# pqxProbjSheet.net
KiCad netlist of a schematic drawn in Altium Designer
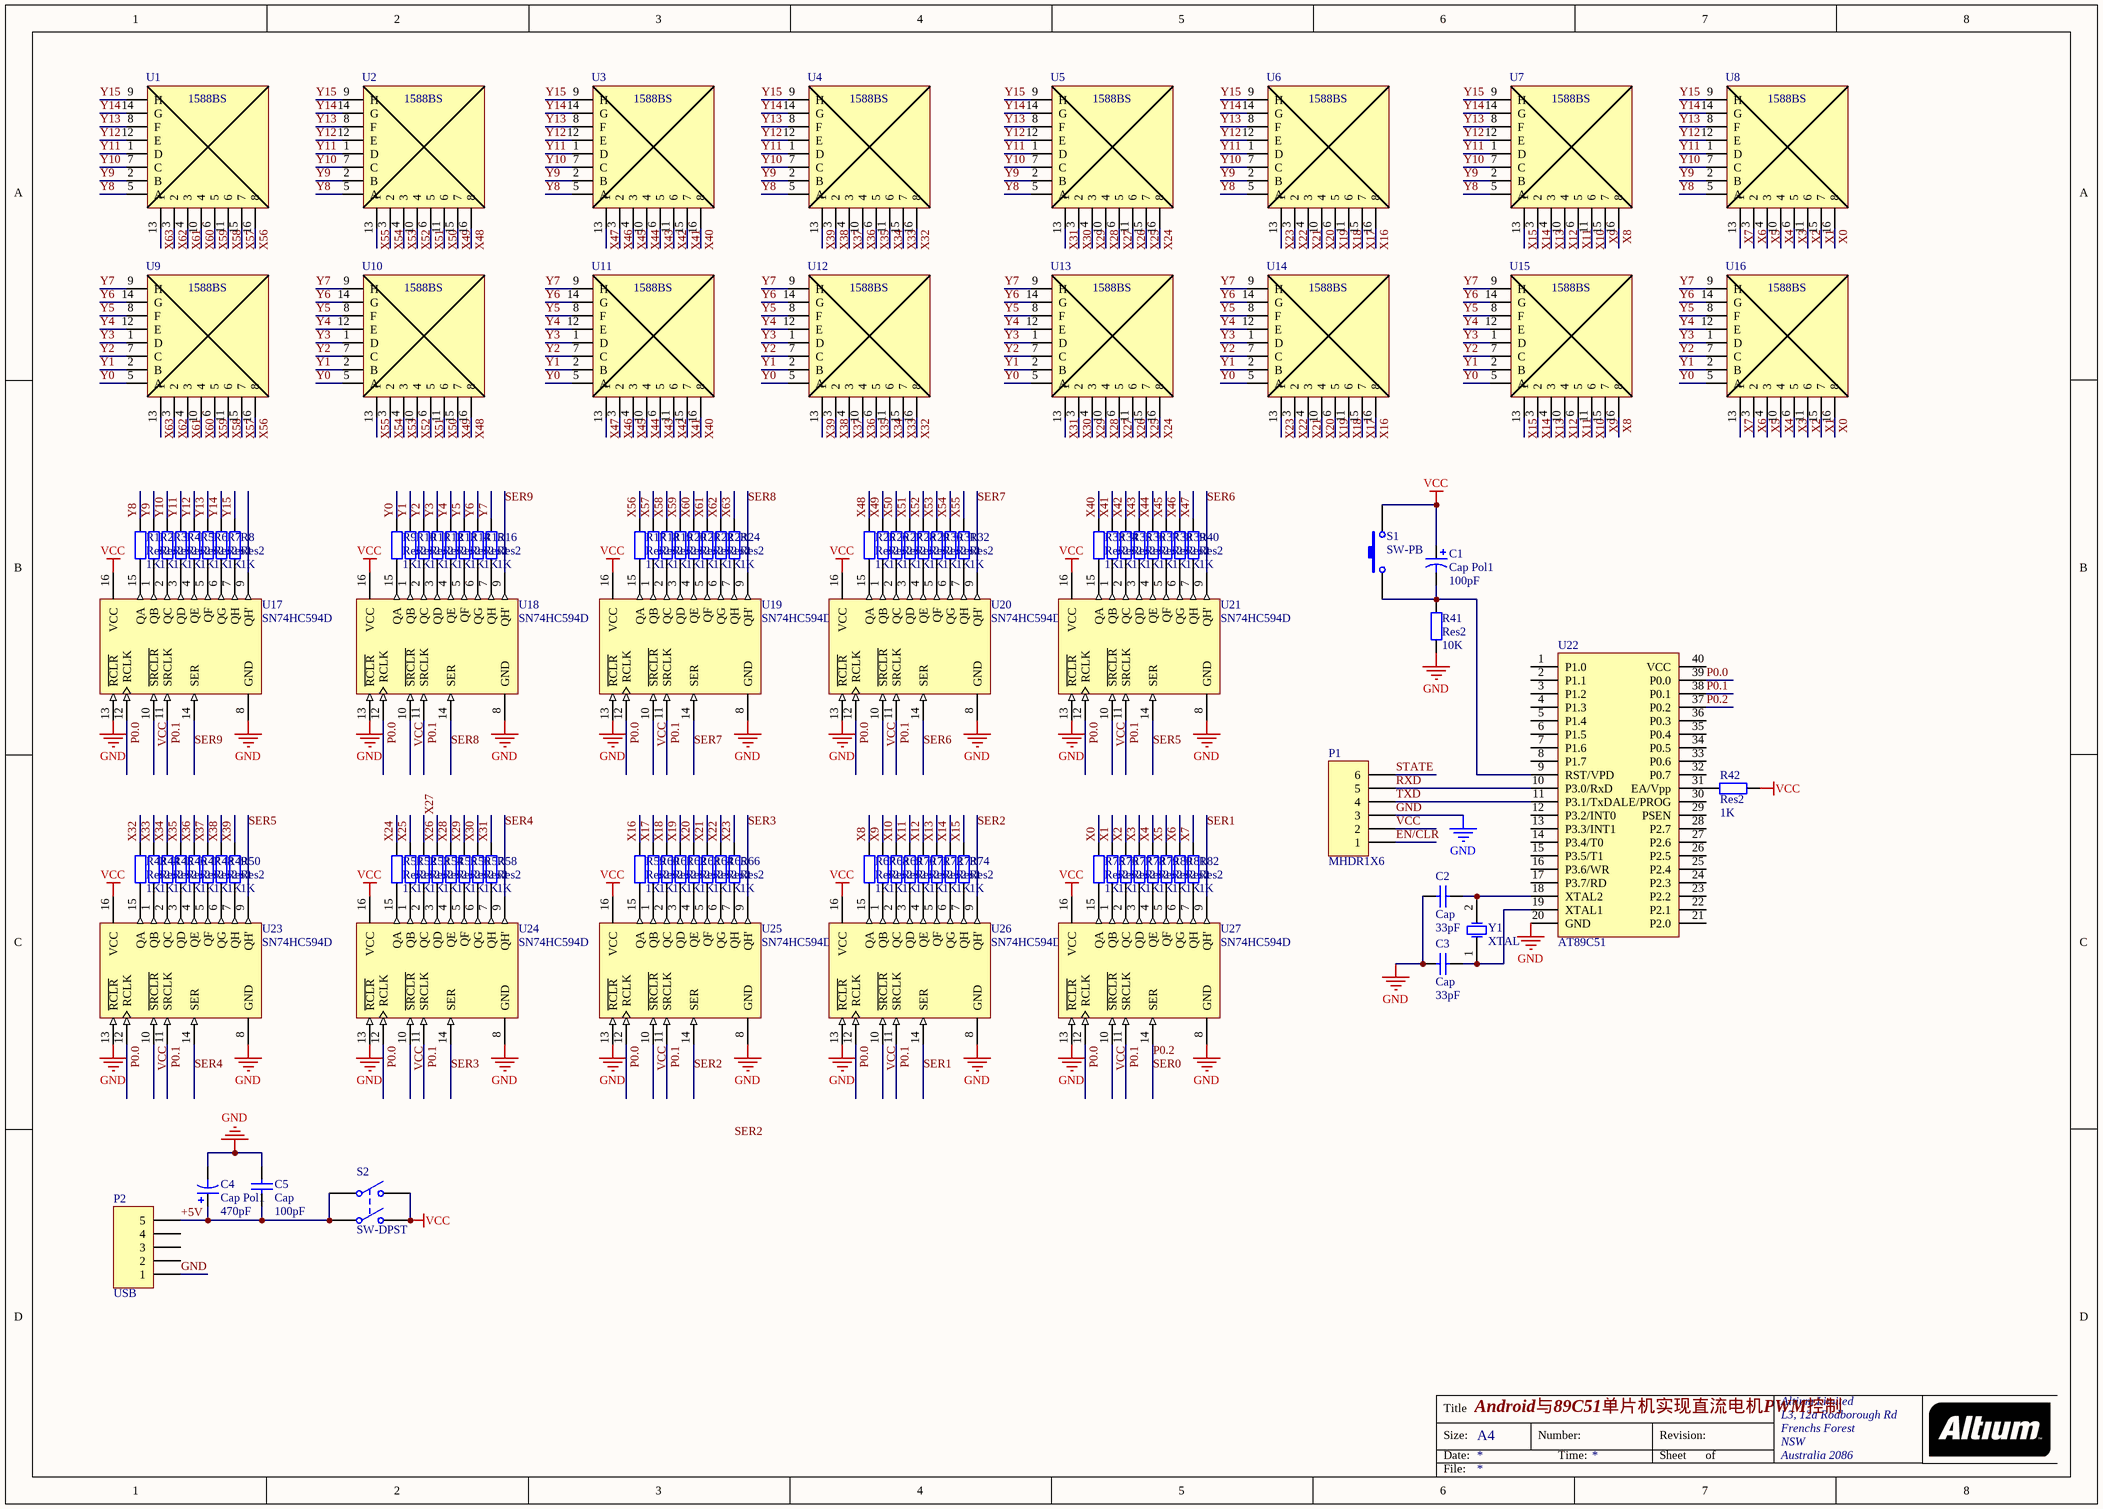
[diagram p0: pqxProbjSheet.SchDoc]

(export (version "E")
  (design (tool "Eeschema 10.0.6"))
  (components
    (comp (ref "C1")
      (value "Cap Pol1")
      (footprint "RB7.6-15")
      (description "Polarized Capacitor (Radial)")
      (fields (field (name "ALTIUM_VALUE") "100pF") (field (name "PUBLISHER") "Altium Limited"))
      (libsource (lib "Miscellaneous Devices") (part "Cap Pol1"))
    )
    (comp (ref "C2")
      (value "Cap")
      (footprint "RAD-0.3")
      (description "Capacitor")
      (fields (field (name "ALTIUM_VALUE") "33pF") (field (name "PUBLISHER") "Altium Limited"))
      (libsource (lib "Miscellaneous Devices") (part "Cap"))
    )
    (comp (ref "C3")
      (value "Cap")
      (footprint "RAD-0.3")
      (description "Capacitor")
      (fields (field (name "ALTIUM_VALUE") "33pF") (field (name "PUBLISHER") "Altium Limited"))
      (libsource (lib "Miscellaneous Devices") (part "Cap"))
    )
    (comp (ref "C4")
      (value "Cap Pol1")
      (footprint "RB7.6-15")
      (description "Polarized Capacitor (Radial)")
      (fields (field (name "ALTIUM_VALUE") "470pF") (field (name "PUBLISHER") "Altium Limited"))
      (libsource (lib "Miscellaneous Devices") (part "Cap Pol1"))
    )
    (comp (ref "C5")
      (value "Cap")
      (footprint "VP32-3.2")
      (description "Capacitor")
      (fields (field (name "ALTIUM_VALUE") "100pF") (field (name "PUBLISHER") "Altium Limited"))
      (libsource (lib "Miscellaneous Devices") (part "Cap"))
    )
    (comp (ref "P1")
      (value "MHDR1X6")
      (footprint "MHDR1X6")
      (description "Header, 6-Pin")
      (fields (field (name "PUBLISHER") "Altium Limited"))
      (libsource (lib "Miscellaneous Connectors") (part "MHDR1X6"))
    )
    (comp (ref "P2")
      (value "USB")
      (footprint "HDR1X5")
      (description "Header, 5-Pin, Right Angle")
      (fields (field (name "PUBLISHER") "Altium Limited"))
      (libsource (lib "Miscellaneous Connectors") (part "Header 5H"))
    )
    (comp (ref "R1")
      (value "Res2")
      (footprint "AXIAL-0.4")
      (description "Resistor")
      (fields (field (name "ALTIUM_VALUE") "1K") (field (name "PUBLISHER") "Altium Limited"))
      (libsource (lib "Miscellaneous Devices") (part "Res2"))
    )
    (comp (ref "R2")
      (value "Res2")
      (footprint "AXIAL-0.4")
      (description "Resistor")
      (fields (field (name "ALTIUM_VALUE") "1K") (field (name "PUBLISHER") "Altium Limited"))
      (libsource (lib "Miscellaneous Devices") (part "Res2"))
    )
    (comp (ref "R3")
      (value "Res2")
      (footprint "AXIAL-0.4")
      (description "Resistor")
      (fields (field (name "ALTIUM_VALUE") "1K") (field (name "PUBLISHER") "Altium Limited"))
      (libsource (lib "Miscellaneous Devices") (part "Res2"))
    )
    (comp (ref "R4")
      (value "Res2")
      (footprint "AXIAL-0.4")
      (description "Resistor")
      (fields (field (name "ALTIUM_VALUE") "1K") (field (name "PUBLISHER") "Altium Limited"))
      (libsource (lib "Miscellaneous Devices") (part "Res2"))
    )
    (comp (ref "R5")
      (value "Res2")
      (footprint "AXIAL-0.4")
      (description "Resistor")
      (fields (field (name "ALTIUM_VALUE") "1K") (field (name "PUBLISHER") "Altium Limited"))
      (libsource (lib "Miscellaneous Devices") (part "Res2"))
    )
    (comp (ref "R6")
      (value "Res2")
      (footprint "AXIAL-0.4")
      (description "Resistor")
      (fields (field (name "ALTIUM_VALUE") "1K") (field (name "PUBLISHER") "Altium Limited"))
      (libsource (lib "Miscellaneous Devices") (part "Res2"))
    )
    (comp (ref "R7")
      (value "Res2")
      (footprint "AXIAL-0.4")
      (description "Resistor")
      (fields (field (name "ALTIUM_VALUE") "1K") (field (name "PUBLISHER") "Altium Limited"))
      (libsource (lib "Miscellaneous Devices") (part "Res2"))
    )
    (comp (ref "R8")
      (value "Res2")
      (footprint "AXIAL-0.4")
      (description "Resistor")
      (fields (field (name "ALTIUM_VALUE") "1K") (field (name "PUBLISHER") "Altium Limited"))
      (libsource (lib "Miscellaneous Devices") (part "Res2"))
    )
    (comp (ref "R9")
      (value "Res2")
      (footprint "AXIAL-0.4")
      (description "Resistor")
      (fields (field (name "ALTIUM_VALUE") "1K") (field (name "PUBLISHER") "Altium Limited"))
      (libsource (lib "Miscellaneous Devices") (part "Res2"))
    )
    (comp (ref "R10")
      (value "Res2")
      (footprint "AXIAL-0.4")
      (description "Resistor")
      (fields (field (name "ALTIUM_VALUE") "1K") (field (name "PUBLISHER") "Altium Limited"))
      (libsource (lib "Miscellaneous Devices") (part "Res2"))
    )
    (comp (ref "R11")
      (value "Res2")
      (footprint "AXIAL-0.4")
      (description "Resistor")
      (fields (field (name "ALTIUM_VALUE") "1K") (field (name "PUBLISHER") "Altium Limited"))
      (libsource (lib "Miscellaneous Devices") (part "Res2"))
    )
    (comp (ref "R12")
      (value "Res2")
      (footprint "AXIAL-0.4")
      (description "Resistor")
      (fields (field (name "ALTIUM_VALUE") "1K") (field (name "PUBLISHER") "Altium Limited"))
      (libsource (lib "Miscellaneous Devices") (part "Res2"))
    )
    (comp (ref "R13")
      (value "Res2")
      (footprint "AXIAL-0.4")
      (description "Resistor")
      (fields (field (name "ALTIUM_VALUE") "1K") (field (name "PUBLISHER") "Altium Limited"))
      (libsource (lib "Miscellaneous Devices") (part "Res2"))
    )
    (comp (ref "R14")
      (value "Res2")
      (footprint "AXIAL-0.4")
      (description "Resistor")
      (fields (field (name "ALTIUM_VALUE") "1K") (field (name "PUBLISHER") "Altium Limited"))
      (libsource (lib "Miscellaneous Devices") (part "Res2"))
    )
    (comp (ref "R15")
      (value "Res2")
      (footprint "AXIAL-0.4")
      (description "Resistor")
      (fields (field (name "ALTIUM_VALUE") "1K") (field (name "PUBLISHER") "Altium Limited"))
      (libsource (lib "Miscellaneous Devices") (part "Res2"))
    )
    (comp (ref "R16")
      (value "Res2")
      (footprint "AXIAL-0.4")
      (description "Resistor")
      (fields (field (name "ALTIUM_VALUE") "1K") (field (name "PUBLISHER") "Altium Limited"))
      (libsource (lib "Miscellaneous Devices") (part "Res2"))
    )
    (comp (ref "R17")
      (value "Res2")
      (footprint "AXIAL-0.4")
      (description "Resistor")
      (fields (field (name "ALTIUM_VALUE") "1K") (field (name "PUBLISHER") "Altium Limited"))
      (libsource (lib "Miscellaneous Devices") (part "Res2"))
    )
    (comp (ref "R18")
      (value "Res2")
      (footprint "AXIAL-0.4")
      (description "Resistor")
      (fields (field (name "ALTIUM_VALUE") "1K") (field (name "PUBLISHER") "Altium Limited"))
      (libsource (lib "Miscellaneous Devices") (part "Res2"))
    )
    (comp (ref "R19")
      (value "Res2")
      (footprint "AXIAL-0.4")
      (description "Resistor")
      (fields (field (name "ALTIUM_VALUE") "1K") (field (name "PUBLISHER") "Altium Limited"))
      (libsource (lib "Miscellaneous Devices") (part "Res2"))
    )
    (comp (ref "R20")
      (value "Res2")
      (footprint "AXIAL-0.4")
      (description "Resistor")
      (fields (field (name "ALTIUM_VALUE") "1K") (field (name "PUBLISHER") "Altium Limited"))
      (libsource (lib "Miscellaneous Devices") (part "Res2"))
    )
    (comp (ref "R21")
      (value "Res2")
      (footprint "AXIAL-0.4")
      (description "Resistor")
      (fields (field (name "ALTIUM_VALUE") "1K") (field (name "PUBLISHER") "Altium Limited"))
      (libsource (lib "Miscellaneous Devices") (part "Res2"))
    )
    (comp (ref "R22")
      (value "Res2")
      (footprint "AXIAL-0.4")
      (description "Resistor")
      (fields (field (name "ALTIUM_VALUE") "1K") (field (name "PUBLISHER") "Altium Limited"))
      (libsource (lib "Miscellaneous Devices") (part "Res2"))
    )
    (comp (ref "R23")
      (value "Res2")
      (footprint "AXIAL-0.4")
      (description "Resistor")
      (fields (field (name "ALTIUM_VALUE") "1K") (field (name "PUBLISHER") "Altium Limited"))
      (libsource (lib "Miscellaneous Devices") (part "Res2"))
    )
    (comp (ref "R24")
      (value "Res2")
      (footprint "AXIAL-0.4")
      (description "Resistor")
      (fields (field (name "ALTIUM_VALUE") "1K") (field (name "PUBLISHER") "Altium Limited"))
      (libsource (lib "Miscellaneous Devices") (part "Res2"))
    )
    (comp (ref "R25")
      (value "Res2")
      (footprint "AXIAL-0.4")
      (description "Resistor")
      (fields (field (name "ALTIUM_VALUE") "1K") (field (name "PUBLISHER") "Altium Limited"))
      (libsource (lib "Miscellaneous Devices") (part "Res2"))
    )
    (comp (ref "R26")
      (value "Res2")
      (footprint "AXIAL-0.4")
      (description "Resistor")
      (fields (field (name "ALTIUM_VALUE") "1K") (field (name "PUBLISHER") "Altium Limited"))
      (libsource (lib "Miscellaneous Devices") (part "Res2"))
    )
    (comp (ref "R27")
      (value "Res2")
      (footprint "AXIAL-0.4")
      (description "Resistor")
      (fields (field (name "ALTIUM_VALUE") "1K") (field (name "PUBLISHER") "Altium Limited"))
      (libsource (lib "Miscellaneous Devices") (part "Res2"))
    )
    (comp (ref "R28")
      (value "Res2")
      (footprint "AXIAL-0.4")
      (description "Resistor")
      (fields (field (name "ALTIUM_VALUE") "1K") (field (name "PUBLISHER") "Altium Limited"))
      (libsource (lib "Miscellaneous Devices") (part "Res2"))
    )
    (comp (ref "R29")
      (value "Res2")
      (footprint "AXIAL-0.4")
      (description "Resistor")
      (fields (field (name "ALTIUM_VALUE") "1K") (field (name "PUBLISHER") "Altium Limited"))
      (libsource (lib "Miscellaneous Devices") (part "Res2"))
    )
    (comp (ref "R30")
      (value "Res2")
      (footprint "AXIAL-0.4")
      (description "Resistor")
      (fields (field (name "ALTIUM_VALUE") "1K") (field (name "PUBLISHER") "Altium Limited"))
      (libsource (lib "Miscellaneous Devices") (part "Res2"))
    )
    (comp (ref "R31")
      (value "Res2")
      (footprint "AXIAL-0.4")
      (description "Resistor")
      (fields (field (name "ALTIUM_VALUE") "1K") (field (name "PUBLISHER") "Altium Limited"))
      (libsource (lib "Miscellaneous Devices") (part "Res2"))
    )
    (comp (ref "R32")
      (value "Res2")
      (footprint "AXIAL-0.4")
      (description "Resistor")
      (fields (field (name "ALTIUM_VALUE") "1K") (field (name "PUBLISHER") "Altium Limited"))
      (libsource (lib "Miscellaneous Devices") (part "Res2"))
    )
    (comp (ref "R33")
      (value "Res2")
      (footprint "AXIAL-0.4")
      (description "Resistor")
      (fields (field (name "ALTIUM_VALUE") "1K") (field (name "PUBLISHER") "Altium Limited"))
      (libsource (lib "Miscellaneous Devices") (part "Res2"))
    )
    (comp (ref "R34")
      (value "Res2")
      (footprint "AXIAL-0.4")
      (description "Resistor")
      (fields (field (name "ALTIUM_VALUE") "1K") (field (name "PUBLISHER") "Altium Limited"))
      (libsource (lib "Miscellaneous Devices") (part "Res2"))
    )
    (comp (ref "R35")
      (value "Res2")
      (footprint "AXIAL-0.4")
      (description "Resistor")
      (fields (field (name "ALTIUM_VALUE") "1K") (field (name "PUBLISHER") "Altium Limited"))
      (libsource (lib "Miscellaneous Devices") (part "Res2"))
    )
    (comp (ref "R36")
      (value "Res2")
      (footprint "AXIAL-0.4")
      (description "Resistor")
      (fields (field (name "ALTIUM_VALUE") "1K") (field (name "PUBLISHER") "Altium Limited"))
      (libsource (lib "Miscellaneous Devices") (part "Res2"))
    )
    (comp (ref "R37")
      (value "Res2")
      (footprint "AXIAL-0.4")
      (description "Resistor")
      (fields (field (name "ALTIUM_VALUE") "1K") (field (name "PUBLISHER") "Altium Limited"))
      (libsource (lib "Miscellaneous Devices") (part "Res2"))
    )
    (comp (ref "R38")
      (value "Res2")
      (footprint "AXIAL-0.4")
      (description "Resistor")
      (fields (field (name "ALTIUM_VALUE") "1K") (field (name "PUBLISHER") "Altium Limited"))
      (libsource (lib "Miscellaneous Devices") (part "Res2"))
    )
    (comp (ref "R39")
      (value "Res2")
      (footprint "AXIAL-0.4")
      (description "Resistor")
      (fields (field (name "ALTIUM_VALUE") "1K") (field (name "PUBLISHER") "Altium Limited"))
      (libsource (lib "Miscellaneous Devices") (part "Res2"))
    )
    (comp (ref "R40")
      (value "Res2")
      (footprint "AXIAL-0.4")
      (description "Resistor")
      (fields (field (name "ALTIUM_VALUE") "1K") (field (name "PUBLISHER") "Altium Limited"))
      (libsource (lib "Miscellaneous Devices") (part "Res2"))
    )
    (comp (ref "R41")
      (value "Res2")
      (footprint "AXIAL-0.4")
      (description "Resistor")
      (fields (field (name "ALTIUM_VALUE") "10K") (field (name "PUBLISHER") "Altium Limited"))
      (libsource (lib "Miscellaneous Devices") (part "Res2"))
    )
    (comp (ref "R42")
      (value "Res2")
      (footprint "AXIAL-0.4")
      (description "Resistor")
      (fields (field (name "ALTIUM_VALUE") "1K") (field (name "PUBLISHER") "Altium Limited"))
      (libsource (lib "") (part "Res2_1"))
    )
    (comp (ref "R43")
      (value "Res2")
      (footprint "AXIAL-0.4")
      (description "Resistor")
      (fields (field (name "ALTIUM_VALUE") "1K") (field (name "PUBLISHER") "Altium Limited"))
      (libsource (lib "Miscellaneous Devices") (part "Res2"))
    )
    (comp (ref "R44")
      (value "Res2")
      (footprint "AXIAL-0.4")
      (description "Resistor")
      (fields (field (name "ALTIUM_VALUE") "1K") (field (name "PUBLISHER") "Altium Limited"))
      (libsource (lib "Miscellaneous Devices") (part "Res2"))
    )
    (comp (ref "R45")
      (value "Res2")
      (footprint "AXIAL-0.4")
      (description "Resistor")
      (fields (field (name "ALTIUM_VALUE") "1K") (field (name "PUBLISHER") "Altium Limited"))
      (libsource (lib "Miscellaneous Devices") (part "Res2"))
    )
    (comp (ref "R46")
      (value "Res2")
      (footprint "AXIAL-0.4")
      (description "Resistor")
      (fields (field (name "ALTIUM_VALUE") "1K") (field (name "PUBLISHER") "Altium Limited"))
      (libsource (lib "Miscellaneous Devices") (part "Res2"))
    )
    (comp (ref "R47")
      (value "Res2")
      (footprint "AXIAL-0.4")
      (description "Resistor")
      (fields (field (name "ALTIUM_VALUE") "1K") (field (name "PUBLISHER") "Altium Limited"))
      (libsource (lib "Miscellaneous Devices") (part "Res2"))
    )
    (comp (ref "R48")
      (value "Res2")
      (footprint "AXIAL-0.4")
      (description "Resistor")
      (fields (field (name "ALTIUM_VALUE") "1K") (field (name "PUBLISHER") "Altium Limited"))
      (libsource (lib "Miscellaneous Devices") (part "Res2"))
    )
    (comp (ref "R49")
      (value "Res2")
      (footprint "AXIAL-0.4")
      (description "Resistor")
      (fields (field (name "ALTIUM_VALUE") "1K") (field (name "PUBLISHER") "Altium Limited"))
      (libsource (lib "Miscellaneous Devices") (part "Res2"))
    )
    (comp (ref "R50")
      (value "Res2")
      (footprint "AXIAL-0.4")
      (description "Resistor")
      (fields (field (name "ALTIUM_VALUE") "1K") (field (name "PUBLISHER") "Altium Limited"))
      (libsource (lib "Miscellaneous Devices") (part "Res2"))
    )
    (comp (ref "R51")
      (value "Res2")
      (footprint "AXIAL-0.4")
      (description "Resistor")
      (fields (field (name "ALTIUM_VALUE") "1K") (field (name "PUBLISHER") "Altium Limited"))
      (libsource (lib "Miscellaneous Devices") (part "Res2"))
    )
    (comp (ref "R52")
      (value "Res2")
      (footprint "AXIAL-0.4")
      (description "Resistor")
      (fields (field (name "ALTIUM_VALUE") "1K") (field (name "PUBLISHER") "Altium Limited"))
      (libsource (lib "Miscellaneous Devices") (part "Res2"))
    )
    (comp (ref "R53")
      (value "Res2")
      (footprint "AXIAL-0.4")
      (description "Resistor")
      (fields (field (name "ALTIUM_VALUE") "1K") (field (name "PUBLISHER") "Altium Limited"))
      (libsource (lib "Miscellaneous Devices") (part "Res2"))
    )
    (comp (ref "R54")
      (value "Res2")
      (footprint "AXIAL-0.4")
      (description "Resistor")
      (fields (field (name "ALTIUM_VALUE") "1K") (field (name "PUBLISHER") "Altium Limited"))
      (libsource (lib "Miscellaneous Devices") (part "Res2"))
    )
    (comp (ref "R55")
      (value "Res2")
      (footprint "AXIAL-0.4")
      (description "Resistor")
      (fields (field (name "ALTIUM_VALUE") "1K") (field (name "PUBLISHER") "Altium Limited"))
      (libsource (lib "Miscellaneous Devices") (part "Res2"))
    )
    (comp (ref "R56")
      (value "Res2")
      (footprint "AXIAL-0.4")
      (description "Resistor")
      (fields (field (name "ALTIUM_VALUE") "1K") (field (name "PUBLISHER") "Altium Limited"))
      (libsource (lib "Miscellaneous Devices") (part "Res2"))
    )
    (comp (ref "R57")
      (value "Res2")
      (footprint "AXIAL-0.4")
      (description "Resistor")
      (fields (field (name "ALTIUM_VALUE") "1K") (field (name "PUBLISHER") "Altium Limited"))
      (libsource (lib "Miscellaneous Devices") (part "Res2"))
    )
    (comp (ref "R58")
      (value "Res2")
      (footprint "AXIAL-0.4")
      (description "Resistor")
      (fields (field (name "ALTIUM_VALUE") "1K") (field (name "PUBLISHER") "Altium Limited"))
      (libsource (lib "Miscellaneous Devices") (part "Res2"))
    )
    (comp (ref "R59")
      (value "Res2")
      (footprint "AXIAL-0.4")
      (description "Resistor")
      (fields (field (name "ALTIUM_VALUE") "1K") (field (name "PUBLISHER") "Altium Limited"))
      (libsource (lib "Miscellaneous Devices") (part "Res2"))
    )
    (comp (ref "R60")
      (value "Res2")
      (footprint "AXIAL-0.4")
      (description "Resistor")
      (fields (field (name "ALTIUM_VALUE") "1K") (field (name "PUBLISHER") "Altium Limited"))
      (libsource (lib "Miscellaneous Devices") (part "Res2"))
    )
    (comp (ref "R61")
      (value "Res2")
      (footprint "AXIAL-0.4")
      (description "Resistor")
      (fields (field (name "ALTIUM_VALUE") "1K") (field (name "PUBLISHER") "Altium Limited"))
      (libsource (lib "Miscellaneous Devices") (part "Res2"))
    )
    (comp (ref "R62")
      (value "Res2")
      (footprint "AXIAL-0.4")
      (description "Resistor")
      (fields (field (name "ALTIUM_VALUE") "1K") (field (name "PUBLISHER") "Altium Limited"))
      (libsource (lib "Miscellaneous Devices") (part "Res2"))
    )
    (comp (ref "R63")
      (value "Res2")
      (footprint "AXIAL-0.4")
      (description "Resistor")
      (fields (field (name "ALTIUM_VALUE") "1K") (field (name "PUBLISHER") "Altium Limited"))
      (libsource (lib "Miscellaneous Devices") (part "Res2"))
    )
    (comp (ref "R64")
      (value "Res2")
      (footprint "AXIAL-0.4")
      (description "Resistor")
      (fields (field (name "ALTIUM_VALUE") "1K") (field (name "PUBLISHER") "Altium Limited"))
      (libsource (lib "Miscellaneous Devices") (part "Res2"))
    )
    (comp (ref "R65")
      (value "Res2")
      (footprint "AXIAL-0.4")
      (description "Resistor")
      (fields (field (name "ALTIUM_VALUE") "1K") (field (name "PUBLISHER") "Altium Limited"))
      (libsource (lib "Miscellaneous Devices") (part "Res2"))
    )
    (comp (ref "R66")
      (value "Res2")
      (footprint "AXIAL-0.4")
      (description "Resistor")
      (fields (field (name "ALTIUM_VALUE") "1K") (field (name "PUBLISHER") "Altium Limited"))
      (libsource (lib "Miscellaneous Devices") (part "Res2"))
    )
    (comp (ref "R67")
      (value "Res2")
      (footprint "AXIAL-0.4")
      (description "Resistor")
      (fields (field (name "ALTIUM_VALUE") "1K") (field (name "PUBLISHER") "Altium Limited"))
      (libsource (lib "Miscellaneous Devices") (part "Res2"))
    )
    (comp (ref "R68")
      (value "Res2")
      (footprint "AXIAL-0.4")
      (description "Resistor")
      (fields (field (name "ALTIUM_VALUE") "1K") (field (name "PUBLISHER") "Altium Limited"))
      (libsource (lib "Miscellaneous Devices") (part "Res2"))
    )
    (comp (ref "R69")
      (value "Res2")
      (footprint "AXIAL-0.4")
      (description "Resistor")
      (fields (field (name "ALTIUM_VALUE") "1K") (field (name "PUBLISHER") "Altium Limited"))
      (libsource (lib "Miscellaneous Devices") (part "Res2"))
    )
    (comp (ref "R70")
      (value "Res2")
      (footprint "AXIAL-0.4")
      (description "Resistor")
      (fields (field (name "ALTIUM_VALUE") "1K") (field (name "PUBLISHER") "Altium Limited"))
      (libsource (lib "Miscellaneous Devices") (part "Res2"))
    )
    (comp (ref "R71")
      (value "Res2")
      (footprint "AXIAL-0.4")
      (description "Resistor")
      (fields (field (name "ALTIUM_VALUE") "1K") (field (name "PUBLISHER") "Altium Limited"))
      (libsource (lib "Miscellaneous Devices") (part "Res2"))
    )
    (comp (ref "R72")
      (value "Res2")
      (footprint "AXIAL-0.4")
      (description "Resistor")
      (fields (field (name "ALTIUM_VALUE") "1K") (field (name "PUBLISHER") "Altium Limited"))
      (libsource (lib "Miscellaneous Devices") (part "Res2"))
    )
    (comp (ref "R73")
      (value "Res2")
      (footprint "AXIAL-0.4")
      (description "Resistor")
      (fields (field (name "ALTIUM_VALUE") "1K") (field (name "PUBLISHER") "Altium Limited"))
      (libsource (lib "Miscellaneous Devices") (part "Res2"))
    )
    (comp (ref "R74")
      (value "Res2")
      (footprint "AXIAL-0.4")
      (description "Resistor")
      (fields (field (name "ALTIUM_VALUE") "1K") (field (name "PUBLISHER") "Altium Limited"))
      (libsource (lib "Miscellaneous Devices") (part "Res2"))
    )
    (comp (ref "R75")
      (value "Res2")
      (footprint "AXIAL-0.4")
      (description "Resistor")
      (fields (field (name "ALTIUM_VALUE") "1K") (field (name "PUBLISHER") "Altium Limited"))
      (libsource (lib "Miscellaneous Devices") (part "Res2"))
    )
    (comp (ref "R76")
      (value "Res2")
      (footprint "AXIAL-0.4")
      (description "Resistor")
      (fields (field (name "ALTIUM_VALUE") "1K") (field (name "PUBLISHER") "Altium Limited"))
      (libsource (lib "Miscellaneous Devices") (part "Res2"))
    )
    (comp (ref "R77")
      (value "Res2")
      (footprint "AXIAL-0.4")
      (description "Resistor")
      (fields (field (name "ALTIUM_VALUE") "1K") (field (name "PUBLISHER") "Altium Limited"))
      (libsource (lib "Miscellaneous Devices") (part "Res2"))
    )
    (comp (ref "R78")
      (value "Res2")
      (footprint "AXIAL-0.4")
      (description "Resistor")
      (fields (field (name "ALTIUM_VALUE") "1K") (field (name "PUBLISHER") "Altium Limited"))
      (libsource (lib "Miscellaneous Devices") (part "Res2"))
    )
    (comp (ref "R79")
      (value "Res2")
      (footprint "AXIAL-0.4")
      (description "Resistor")
      (fields (field (name "ALTIUM_VALUE") "1K") (field (name "PUBLISHER") "Altium Limited"))
      (libsource (lib "Miscellaneous Devices") (part "Res2"))
    )
    (comp (ref "R80")
      (value "Res2")
      (footprint "AXIAL-0.4")
      (description "Resistor")
      (fields (field (name "ALTIUM_VALUE") "1K") (field (name "PUBLISHER") "Altium Limited"))
      (libsource (lib "Miscellaneous Devices") (part "Res2"))
    )
    (comp (ref "R81")
      (value "Res2")
      (footprint "AXIAL-0.4")
      (description "Resistor")
      (fields (field (name "ALTIUM_VALUE") "1K") (field (name "PUBLISHER") "Altium Limited"))
      (libsource (lib "Miscellaneous Devices") (part "Res2"))
    )
    (comp (ref "R82")
      (value "Res2")
      (footprint "AXIAL-0.4")
      (description "Resistor")
      (fields (field (name "ALTIUM_VALUE") "1K") (field (name "PUBLISHER") "Altium Limited"))
      (libsource (lib "Miscellaneous Devices") (part "Res2"))
    )
    (comp (ref "S1")
      (value "SW-PB")
      (footprint "SPST-2")
      (description "Switch")
      (fields (field (name "PUBLISHER") "Altium Limited"))
      (libsource (lib "Miscellaneous Devices") (part "SW-PB"))
    )
    (comp (ref "S2")
      (value "SW-DPST")
      (footprint "DPST-4")
      (description "Double-Pole, Single-Throw Switch")
      (fields (field (name "PUBLISHER") "Altium Limited"))
      (libsource (lib "Miscellaneous Devices") (part "SW-DPST"))
    )
    (comp (ref "U1")
      (value "1588BS")
      (footprint "1588BS_16Pin")
      (libsource (lib "panQuanXing") (part "1588BS点阵"))
    )
    (comp (ref "U2")
      (value "1588BS")
      (footprint "1588BS_16Pin")
      (libsource (lib "panQuanXing") (part "1588BS点阵"))
    )
    (comp (ref "U3")
      (value "1588BS")
      (footprint "1588BS_16Pin")
      (libsource (lib "panQuanXing") (part "1588BS点阵"))
    )
    (comp (ref "U4")
      (value "1588BS")
      (footprint "1588BS_16Pin")
      (libsource (lib "panQuanXing") (part "1588BS点阵"))
    )
    (comp (ref "U5")
      (value "1588BS")
      (footprint "1588BS_16Pin")
      (libsource (lib "panQuanXing") (part "1588BS点阵"))
    )
    (comp (ref "U6")
      (value "1588BS")
      (footprint "1588BS_16Pin")
      (libsource (lib "panQuanXing") (part "1588BS点阵"))
    )
    (comp (ref "U7")
      (value "1588BS")
      (footprint "1588BS_16Pin")
      (libsource (lib "panQuanXing") (part "1588BS点阵"))
    )
    (comp (ref "U8")
      (value "1588BS")
      (footprint "1588BS_16Pin")
      (libsource (lib "panQuanXing") (part "1588BS点阵"))
    )
    (comp (ref "U9")
      (value "1588BS")
      (footprint "1588BS_16Pin")
      (libsource (lib "panQuanXing") (part "1588BS点阵"))
    )
    (comp (ref "U10")
      (value "1588BS")
      (footprint "1588BS_16Pin")
      (libsource (lib "panQuanXing") (part "1588BS点阵"))
    )
    (comp (ref "U11")
      (value "1588BS")
      (footprint "1588BS_16Pin")
      (libsource (lib "panQuanXing") (part "1588BS点阵"))
    )
    (comp (ref "U12")
      (value "1588BS")
      (footprint "1588BS_16Pin")
      (libsource (lib "panQuanXing") (part "1588BS点阵"))
    )
    (comp (ref "U13")
      (value "1588BS")
      (footprint "1588BS_16Pin")
      (libsource (lib "panQuanXing") (part "1588BS点阵"))
    )
    (comp (ref "U14")
      (value "1588BS")
      (footprint "1588BS_16Pin")
      (libsource (lib "panQuanXing") (part "1588BS点阵"))
    )
    (comp (ref "U15")
      (value "1588BS")
      (footprint "1588BS_16Pin")
      (libsource (lib "panQuanXing") (part "1588BS点阵"))
    )
    (comp (ref "U16")
      (value "1588BS")
      (footprint "1588BS_16Pin")
      (libsource (lib "panQuanXing") (part "1588BS点阵"))
    )
    (comp (ref "U17")
      (value "SN74HC594D")
      (footprint "D016_N")
      (description "8-Bit Shift Register with Output Registers")
      (fields (field (name "PUBLISHER") "Altium Limited"))
      (libsource (lib "TI Logic Register") (part "SN74HC594D"))
    )
    (comp (ref "U18")
      (value "SN74HC594D")
      (footprint "D016_N")
      (description "8-Bit Shift Register with Output Registers")
      (fields (field (name "PUBLISHER") "Altium Limited"))
      (libsource (lib "TI Logic Register") (part "SN74HC594D"))
    )
    (comp (ref "U19")
      (value "SN74HC594D")
      (footprint "D016_N")
      (description "8-Bit Shift Register with Output Registers")
      (fields (field (name "PUBLISHER") "Altium Limited"))
      (libsource (lib "TI Logic Register") (part "SN74HC594D"))
    )
    (comp (ref "U20")
      (value "SN74HC594D")
      (footprint "D016_N")
      (description "8-Bit Shift Register with Output Registers")
      (fields (field (name "PUBLISHER") "Altium Limited"))
      (libsource (lib "TI Logic Register") (part "SN74HC594D"))
    )
    (comp (ref "U21")
      (value "SN74HC594D")
      (footprint "D016_N")
      (description "8-Bit Shift Register with Output Registers")
      (fields (field (name "PUBLISHER") "Altium Limited"))
      (libsource (lib "TI Logic Register") (part "SN74HC594D"))
    )
    (comp (ref "U22") (value "AT89C51") (footprint "DIP40") (libsource (lib "fnsSCH") (part "89C51")))
    (comp (ref "U23")
      (value "SN74HC594D")
      (footprint "D016_N")
      (description "8-Bit Shift Register with Output Registers")
      (fields (field (name "PUBLISHER") "Altium Limited"))
      (libsource (lib "TI Logic Register") (part "SN74HC594D"))
    )
    (comp (ref "U24")
      (value "SN74HC594D")
      (footprint "D016_N")
      (description "8-Bit Shift Register with Output Registers")
      (fields (field (name "PUBLISHER") "Altium Limited"))
      (libsource (lib "TI Logic Register") (part "SN74HC594D"))
    )
    (comp (ref "U25")
      (value "SN74HC594D")
      (footprint "D016_N")
      (description "8-Bit Shift Register with Output Registers")
      (fields (field (name "PUBLISHER") "Altium Limited"))
      (libsource (lib "TI Logic Register") (part "SN74HC594D"))
    )
    (comp (ref "U26")
      (value "SN74HC594D")
      (footprint "D016_N")
      (description "8-Bit Shift Register with Output Registers")
      (fields (field (name "PUBLISHER") "Altium Limited"))
      (libsource (lib "TI Logic Register") (part "SN74HC594D"))
    )
    (comp (ref "U27")
      (value "SN74HC594D")
      (footprint "D016_N")
      (description "8-Bit Shift Register with Output Registers")
      (fields (field (name "PUBLISHER") "Altium Limited"))
      (libsource (lib "TI Logic Register") (part "SN74HC594D"))
    )
    (comp (ref "Y1")
      (value "XTAL")
      (footprint "R38")
      (description "Crystal Oscillator")
      (fields (field (name "PUBLISHER") "Altium Limited"))
      (libsource (lib "Miscellaneous Devices") (part "XTAL"))
    )
  )
  (nets
    (net (code "1") (name "/+5V") (class "Default")
      (node (ref "C4") (pin "1") (pinfunction "1_1") (pintype "passive"))
      (node (ref "C5") (pin "1") (pinfunction "1_1") (pintype "passive"))
      (node (ref "P2") (pin "5") (pinfunction "5_5") (pintype "passive"))
      (node (ref "S2") (pin "1") (pinfunction "COMMON1_1") (pintype "passive"))
      (node (ref "S2") (pin "3") (pinfunction "COMMON2_3") (pintype "passive"))
    )
    (net (code "2") (name "/EN{slash}CLR") (class "Default")
      (node (ref "P1") (pin "1") (pinfunction "1_1") (pintype "passive"))
    )
    (net (code "3") (name "/P0.0") (class "Default")
      (node (ref "U17") (pin "12") (pinfunction "RCLK_12") (pintype "input"))
      (node (ref "U18") (pin "12") (pinfunction "RCLK_12") (pintype "input"))
      (node (ref "U19") (pin "12") (pinfunction "RCLK_12") (pintype "input"))
      (node (ref "U20") (pin "12") (pinfunction "RCLK_12") (pintype "input"))
      (node (ref "U21") (pin "12") (pinfunction "RCLK_12") (pintype "input"))
      (node (ref "U22") (pin "39") (pinfunction "P0.0_39") (pintype "passive"))
      (node (ref "U23") (pin "12") (pinfunction "RCLK_12") (pintype "input"))
      (node (ref "U24") (pin "12") (pinfunction "RCLK_12") (pintype "input"))
      (node (ref "U25") (pin "12") (pinfunction "RCLK_12") (pintype "input"))
      (node (ref "U26") (pin "12") (pinfunction "RCLK_12") (pintype "input"))
      (node (ref "U27") (pin "12") (pinfunction "RCLK_12") (pintype "input"))
    )
    (net (code "4") (name "/P0.1") (class "Default")
      (node (ref "U17") (pin "11") (pinfunction "SRCLK_11") (pintype "input"))
      (node (ref "U18") (pin "11") (pinfunction "SRCLK_11") (pintype "input"))
      (node (ref "U19") (pin "11") (pinfunction "SRCLK_11") (pintype "input"))
      (node (ref "U20") (pin "11") (pinfunction "SRCLK_11") (pintype "input"))
      (node (ref "U21") (pin "11") (pinfunction "SRCLK_11") (pintype "input"))
      (node (ref "U22") (pin "38") (pinfunction "P0.1_38") (pintype "passive"))
      (node (ref "U23") (pin "11") (pinfunction "SRCLK_11") (pintype "input"))
      (node (ref "U24") (pin "11") (pinfunction "SRCLK_11") (pintype "input"))
      (node (ref "U25") (pin "11") (pinfunction "SRCLK_11") (pintype "input"))
      (node (ref "U26") (pin "11") (pinfunction "SRCLK_11") (pintype "input"))
      (node (ref "U27") (pin "11") (pinfunction "SRCLK_11") (pintype "input"))
    )
    (net (code "5") (name "/P0.2") (class "Default")
      (node (ref "U22") (pin "37") (pinfunction "P0.2_37") (pintype "passive"))
      (node (ref "U27") (pin "14") (pinfunction "SER_14") (pintype "input"))
    )
    (net (code "6") (name "/RXD") (class "Default")
      (node (ref "P1") (pin "5") (pinfunction "5_5") (pintype "passive"))
      (node (ref "U22") (pin "10") (pinfunction "P3.0/RxD_10") (pintype "passive"))
    )
    (net (code "7") (name "/SER1") (class "Default")
      (node (ref "U26") (pin "14") (pinfunction "SER_14") (pintype "input"))
      (node (ref "U27") (pin "9") (pinfunction "QH'_9") (pintype "output"))
    )
    (net (code "8") (name "/SER2") (class "Default")
      (node (ref "U25") (pin "14") (pinfunction "SER_14") (pintype "input"))
      (node (ref "U26") (pin "9") (pinfunction "QH'_9") (pintype "output"))
    )
    (net (code "9") (name "/SER3") (class "Default")
      (node (ref "U24") (pin "14") (pinfunction "SER_14") (pintype "input"))
      (node (ref "U25") (pin "9") (pinfunction "QH'_9") (pintype "output"))
    )
    (net (code "10") (name "/SER4") (class "Default")
      (node (ref "U23") (pin "14") (pinfunction "SER_14") (pintype "input"))
      (node (ref "U24") (pin "9") (pinfunction "QH'_9") (pintype "output"))
    )
    (net (code "11") (name "/SER5") (class "Default")
      (node (ref "U21") (pin "14") (pinfunction "SER_14") (pintype "input"))
      (node (ref "U23") (pin "9") (pinfunction "QH'_9") (pintype "output"))
    )
    (net (code "12") (name "/SER6") (class "Default")
      (node (ref "U20") (pin "14") (pinfunction "SER_14") (pintype "input"))
      (node (ref "U21") (pin "9") (pinfunction "QH'_9") (pintype "output"))
    )
    (net (code "13") (name "/SER7") (class "Default")
      (node (ref "U19") (pin "14") (pinfunction "SER_14") (pintype "input"))
      (node (ref "U20") (pin "9") (pinfunction "QH'_9") (pintype "output"))
    )
    (net (code "14") (name "/SER8") (class "Default")
      (node (ref "U18") (pin "14") (pinfunction "SER_14") (pintype "input"))
      (node (ref "U19") (pin "9") (pinfunction "QH'_9") (pintype "output"))
    )
    (net (code "15") (name "/SER9") (class "Default")
      (node (ref "U17") (pin "14") (pinfunction "SER_14") (pintype "input"))
      (node (ref "U18") (pin "9") (pinfunction "QH'_9") (pintype "output"))
    )
    (net (code "16") (name "/STATE") (class "Default")
      (node (ref "P1") (pin "6") (pinfunction "6_6") (pintype "passive"))
    )
    (net (code "17") (name "/TXD") (class "Default")
      (node (ref "P1") (pin "4") (pinfunction "4_4") (pintype "passive"))
      (node (ref "U22") (pin "11") (pinfunction "P3.1/TxD_11") (pintype "passive"))
    )
    (net (code "18") (name "/X0") (class "Default")
      (node (ref "R75") (pin "2") (pinfunction "2_2") (pintype "passive"))
      (node (ref "U16") (pin "16") (pinfunction "8_16") (pintype "passive"))
      (node (ref "U8") (pin "16") (pinfunction "8_16") (pintype "passive"))
    )
    (net (code "19") (name "/X1") (class "Default")
      (node (ref "R76") (pin "2") (pinfunction "2_2") (pintype "passive"))
      (node (ref "U16") (pin "15") (pinfunction "7_15") (pintype "passive"))
      (node (ref "U8") (pin "15") (pinfunction "7_15") (pintype "passive"))
    )
    (net (code "20") (name "/X2") (class "Default")
      (node (ref "R77") (pin "2") (pinfunction "2_2") (pintype "passive"))
      (node (ref "U16") (pin "11") (pinfunction "6_11") (pintype "passive"))
      (node (ref "U8") (pin "11") (pinfunction "6_11") (pintype "passive"))
    )
    (net (code "21") (name "/X3") (class "Default")
      (node (ref "R78") (pin "2") (pinfunction "2_2") (pintype "passive"))
      (node (ref "U16") (pin "6") (pinfunction "5_6") (pintype "passive"))
      (node (ref "U8") (pin "6") (pinfunction "5_6") (pintype "passive"))
    )
    (net (code "22") (name "/X4") (class "Default")
      (node (ref "R79") (pin "2") (pinfunction "2_2") (pintype "passive"))
      (node (ref "U16") (pin "10") (pinfunction "4_10") (pintype "passive"))
      (node (ref "U8") (pin "10") (pinfunction "4_10") (pintype "passive"))
    )
    (net (code "23") (name "/X5") (class "Default")
      (node (ref "R80") (pin "2") (pinfunction "2_2") (pintype "passive"))
      (node (ref "U16") (pin "4") (pinfunction "3_4") (pintype "passive"))
      (node (ref "U8") (pin "4") (pinfunction "3_4") (pintype "passive"))
    )
    (net (code "24") (name "/X6") (class "Default")
      (node (ref "R81") (pin "2") (pinfunction "2_2") (pintype "passive"))
      (node (ref "U16") (pin "3") (pinfunction "2_3") (pintype "passive"))
      (node (ref "U8") (pin "3") (pinfunction "2_3") (pintype "passive"))
    )
    (net (code "25") (name "/X7") (class "Default")
      (node (ref "R82") (pin "2") (pinfunction "2_2") (pintype "passive"))
      (node (ref "U16") (pin "13") (pinfunction "1_13") (pintype "passive"))
      (node (ref "U8") (pin "13") (pinfunction "1_13") (pintype "passive"))
    )
    (net (code "26") (name "/X8") (class "Default")
      (node (ref "R67") (pin "2") (pinfunction "2_2") (pintype "passive"))
      (node (ref "U15") (pin "16") (pinfunction "8_16") (pintype "passive"))
      (node (ref "U7") (pin "16") (pinfunction "8_16") (pintype "passive"))
    )
    (net (code "27") (name "/X9") (class "Default")
      (node (ref "R68") (pin "2") (pinfunction "2_2") (pintype "passive"))
      (node (ref "U15") (pin "15") (pinfunction "7_15") (pintype "passive"))
      (node (ref "U7") (pin "15") (pinfunction "7_15") (pintype "passive"))
    )
    (net (code "28") (name "/X10") (class "Default")
      (node (ref "R69") (pin "2") (pinfunction "2_2") (pintype "passive"))
      (node (ref "U15") (pin "11") (pinfunction "6_11") (pintype "passive"))
      (node (ref "U7") (pin "11") (pinfunction "6_11") (pintype "passive"))
    )
    (net (code "29") (name "/X11") (class "Default")
      (node (ref "R70") (pin "2") (pinfunction "2_2") (pintype "passive"))
      (node (ref "U15") (pin "6") (pinfunction "5_6") (pintype "passive"))
      (node (ref "U7") (pin "6") (pinfunction "5_6") (pintype "passive"))
    )
    (net (code "30") (name "/X12") (class "Default")
      (node (ref "R71") (pin "2") (pinfunction "2_2") (pintype "passive"))
      (node (ref "U15") (pin "10") (pinfunction "4_10") (pintype "passive"))
      (node (ref "U7") (pin "10") (pinfunction "4_10") (pintype "passive"))
    )
    (net (code "31") (name "/X13") (class "Default")
      (node (ref "R72") (pin "2") (pinfunction "2_2") (pintype "passive"))
      (node (ref "U15") (pin "4") (pinfunction "3_4") (pintype "passive"))
      (node (ref "U7") (pin "4") (pinfunction "3_4") (pintype "passive"))
    )
    (net (code "32") (name "/X14") (class "Default")
      (node (ref "R73") (pin "2") (pinfunction "2_2") (pintype "passive"))
      (node (ref "U15") (pin "3") (pinfunction "2_3") (pintype "passive"))
      (node (ref "U7") (pin "3") (pinfunction "2_3") (pintype "passive"))
    )
    (net (code "33") (name "/X15") (class "Default")
      (node (ref "R74") (pin "2") (pinfunction "2_2") (pintype "passive"))
      (node (ref "U15") (pin "13") (pinfunction "1_13") (pintype "passive"))
      (node (ref "U7") (pin "13") (pinfunction "1_13") (pintype "passive"))
    )
    (net (code "34") (name "/X16") (class "Default")
      (node (ref "R59") (pin "2") (pinfunction "2_2") (pintype "passive"))
      (node (ref "U14") (pin "16") (pinfunction "8_16") (pintype "passive"))
      (node (ref "U6") (pin "16") (pinfunction "8_16") (pintype "passive"))
    )
    (net (code "35") (name "/X17") (class "Default")
      (node (ref "R60") (pin "2") (pinfunction "2_2") (pintype "passive"))
      (node (ref "U14") (pin "15") (pinfunction "7_15") (pintype "passive"))
      (node (ref "U6") (pin "15") (pinfunction "7_15") (pintype "passive"))
    )
    (net (code "36") (name "/X18") (class "Default")
      (node (ref "R61") (pin "2") (pinfunction "2_2") (pintype "passive"))
      (node (ref "U14") (pin "11") (pinfunction "6_11") (pintype "passive"))
      (node (ref "U6") (pin "11") (pinfunction "6_11") (pintype "passive"))
    )
    (net (code "37") (name "/X19") (class "Default")
      (node (ref "R62") (pin "2") (pinfunction "2_2") (pintype "passive"))
      (node (ref "U14") (pin "6") (pinfunction "5_6") (pintype "passive"))
      (node (ref "U6") (pin "6") (pinfunction "5_6") (pintype "passive"))
    )
    (net (code "38") (name "/X20") (class "Default")
      (node (ref "R63") (pin "2") (pinfunction "2_2") (pintype "passive"))
      (node (ref "U14") (pin "10") (pinfunction "4_10") (pintype "passive"))
      (node (ref "U6") (pin "10") (pinfunction "4_10") (pintype "passive"))
    )
    (net (code "39") (name "/X21") (class "Default")
      (node (ref "R64") (pin "2") (pinfunction "2_2") (pintype "passive"))
      (node (ref "U14") (pin "4") (pinfunction "3_4") (pintype "passive"))
      (node (ref "U6") (pin "4") (pinfunction "3_4") (pintype "passive"))
    )
    (net (code "40") (name "/X22") (class "Default")
      (node (ref "R65") (pin "2") (pinfunction "2_2") (pintype "passive"))
      (node (ref "U14") (pin "3") (pinfunction "2_3") (pintype "passive"))
      (node (ref "U6") (pin "3") (pinfunction "2_3") (pintype "passive"))
    )
    (net (code "41") (name "/X23") (class "Default")
      (node (ref "R66") (pin "2") (pinfunction "2_2") (pintype "passive"))
      (node (ref "U14") (pin "13") (pinfunction "1_13") (pintype "passive"))
      (node (ref "U6") (pin "13") (pinfunction "1_13") (pintype "passive"))
    )
    (net (code "42") (name "/X24") (class "Default")
      (node (ref "R51") (pin "2") (pinfunction "2_2") (pintype "passive"))
      (node (ref "U13") (pin "16") (pinfunction "8_16") (pintype "passive"))
      (node (ref "U5") (pin "16") (pinfunction "8_16") (pintype "passive"))
    )
    (net (code "43") (name "/X25") (class "Default")
      (node (ref "R52") (pin "2") (pinfunction "2_2") (pintype "passive"))
      (node (ref "U13") (pin "15") (pinfunction "7_15") (pintype "passive"))
      (node (ref "U5") (pin "15") (pinfunction "7_15") (pintype "passive"))
    )
    (net (code "44") (name "/X26") (class "Default")
      (node (ref "R54") (pin "2") (pinfunction "2_2") (pintype "passive"))
      (node (ref "U13") (pin "11") (pinfunction "6_11") (pintype "passive"))
      (node (ref "U13") (pin "6") (pinfunction "5_6") (pintype "passive"))
      (node (ref "U5") (pin "11") (pinfunction "6_11") (pintype "passive"))
      (node (ref "U5") (pin "6") (pinfunction "5_6") (pintype "passive"))
    )
    (net (code "45") (name "/X28") (class "Default")
      (node (ref "R55") (pin "2") (pinfunction "2_2") (pintype "passive"))
      (node (ref "U13") (pin "10") (pinfunction "4_10") (pintype "passive"))
      (node (ref "U5") (pin "10") (pinfunction "4_10") (pintype "passive"))
    )
    (net (code "46") (name "/X29") (class "Default")
      (node (ref "R56") (pin "2") (pinfunction "2_2") (pintype "passive"))
      (node (ref "U13") (pin "4") (pinfunction "3_4") (pintype "passive"))
      (node (ref "U5") (pin "4") (pinfunction "3_4") (pintype "passive"))
    )
    (net (code "47") (name "/X30") (class "Default")
      (node (ref "R57") (pin "2") (pinfunction "2_2") (pintype "passive"))
      (node (ref "U13") (pin "3") (pinfunction "2_3") (pintype "passive"))
      (node (ref "U5") (pin "3") (pinfunction "2_3") (pintype "passive"))
    )
    (net (code "48") (name "/X31") (class "Default")
      (node (ref "R58") (pin "2") (pinfunction "2_2") (pintype "passive"))
      (node (ref "U13") (pin "13") (pinfunction "1_13") (pintype "passive"))
      (node (ref "U5") (pin "13") (pinfunction "1_13") (pintype "passive"))
    )
    (net (code "49") (name "/X32") (class "Default")
      (node (ref "R43") (pin "2") (pinfunction "2_2") (pintype "passive"))
      (node (ref "U12") (pin "16") (pinfunction "8_16") (pintype "passive"))
      (node (ref "U4") (pin "16") (pinfunction "8_16") (pintype "passive"))
    )
    (net (code "50") (name "/X33") (class "Default")
      (node (ref "R44") (pin "2") (pinfunction "2_2") (pintype "passive"))
      (node (ref "U12") (pin "15") (pinfunction "7_15") (pintype "passive"))
      (node (ref "U4") (pin "15") (pinfunction "7_15") (pintype "passive"))
    )
    (net (code "51") (name "/X34") (class "Default")
      (node (ref "R45") (pin "2") (pinfunction "2_2") (pintype "passive"))
      (node (ref "U12") (pin "11") (pinfunction "6_11") (pintype "passive"))
      (node (ref "U4") (pin "11") (pinfunction "6_11") (pintype "passive"))
    )
    (net (code "52") (name "/X35") (class "Default")
      (node (ref "R46") (pin "2") (pinfunction "2_2") (pintype "passive"))
      (node (ref "U12") (pin "6") (pinfunction "5_6") (pintype "passive"))
      (node (ref "U4") (pin "6") (pinfunction "5_6") (pintype "passive"))
    )
    (net (code "53") (name "/X36") (class "Default")
      (node (ref "R47") (pin "2") (pinfunction "2_2") (pintype "passive"))
      (node (ref "U12") (pin "10") (pinfunction "4_10") (pintype "passive"))
      (node (ref "U4") (pin "10") (pinfunction "4_10") (pintype "passive"))
    )
    (net (code "54") (name "/X37") (class "Default")
      (node (ref "R48") (pin "2") (pinfunction "2_2") (pintype "passive"))
      (node (ref "U12") (pin "4") (pinfunction "3_4") (pintype "passive"))
      (node (ref "U4") (pin "4") (pinfunction "3_4") (pintype "passive"))
    )
    (net (code "55") (name "/X38") (class "Default")
      (node (ref "R49") (pin "2") (pinfunction "2_2") (pintype "passive"))
      (node (ref "U12") (pin "3") (pinfunction "2_3") (pintype "passive"))
      (node (ref "U4") (pin "3") (pinfunction "2_3") (pintype "passive"))
    )
    (net (code "56") (name "/X39") (class "Default")
      (node (ref "R50") (pin "2") (pinfunction "2_2") (pintype "passive"))
      (node (ref "U12") (pin "13") (pinfunction "1_13") (pintype "passive"))
      (node (ref "U4") (pin "13") (pinfunction "1_13") (pintype "passive"))
    )
    (net (code "57") (name "/X40") (class "Default")
      (node (ref "R33") (pin "2") (pinfunction "2_2") (pintype "passive"))
      (node (ref "U11") (pin "16") (pinfunction "8_16") (pintype "passive"))
      (node (ref "U3") (pin "16") (pinfunction "8_16") (pintype "passive"))
    )
    (net (code "58") (name "/X41") (class "Default")
      (node (ref "R34") (pin "2") (pinfunction "2_2") (pintype "passive"))
      (node (ref "U11") (pin "15") (pinfunction "7_15") (pintype "passive"))
      (node (ref "U3") (pin "15") (pinfunction "7_15") (pintype "passive"))
    )
    (net (code "59") (name "/X42") (class "Default")
      (node (ref "R35") (pin "2") (pinfunction "2_2") (pintype "passive"))
      (node (ref "U11") (pin "11") (pinfunction "6_11") (pintype "passive"))
      (node (ref "U3") (pin "11") (pinfunction "6_11") (pintype "passive"))
    )
    (net (code "60") (name "/X43") (class "Default")
      (node (ref "R36") (pin "2") (pinfunction "2_2") (pintype "passive"))
      (node (ref "U11") (pin "6") (pinfunction "5_6") (pintype "passive"))
      (node (ref "U3") (pin "6") (pinfunction "5_6") (pintype "passive"))
    )
    (net (code "61") (name "/X44") (class "Default")
      (node (ref "R37") (pin "2") (pinfunction "2_2") (pintype "passive"))
      (node (ref "U11") (pin "10") (pinfunction "4_10") (pintype "passive"))
      (node (ref "U3") (pin "10") (pinfunction "4_10") (pintype "passive"))
    )
    (net (code "62") (name "/X45") (class "Default")
      (node (ref "R38") (pin "2") (pinfunction "2_2") (pintype "passive"))
      (node (ref "U11") (pin "4") (pinfunction "3_4") (pintype "passive"))
      (node (ref "U3") (pin "4") (pinfunction "3_4") (pintype "passive"))
    )
    (net (code "63") (name "/X46") (class "Default")
      (node (ref "R39") (pin "2") (pinfunction "2_2") (pintype "passive"))
      (node (ref "U11") (pin "3") (pinfunction "2_3") (pintype "passive"))
      (node (ref "U3") (pin "3") (pinfunction "2_3") (pintype "passive"))
    )
    (net (code "64") (name "/X47") (class "Default")
      (node (ref "R40") (pin "2") (pinfunction "2_2") (pintype "passive"))
      (node (ref "U11") (pin "13") (pinfunction "1_13") (pintype "passive"))
      (node (ref "U3") (pin "13") (pinfunction "1_13") (pintype "passive"))
    )
    (net (code "65") (name "/X48") (class "Default")
      (node (ref "R25") (pin "2") (pinfunction "2_2") (pintype "passive"))
      (node (ref "U10") (pin "16") (pinfunction "8_16") (pintype "passive"))
      (node (ref "U2") (pin "16") (pinfunction "8_16") (pintype "passive"))
    )
    (net (code "66") (name "/X49") (class "Default")
      (node (ref "R26") (pin "2") (pinfunction "2_2") (pintype "passive"))
      (node (ref "U10") (pin "15") (pinfunction "7_15") (pintype "passive"))
      (node (ref "U2") (pin "15") (pinfunction "7_15") (pintype "passive"))
    )
    (net (code "67") (name "/X50") (class "Default")
      (node (ref "R27") (pin "2") (pinfunction "2_2") (pintype "passive"))
      (node (ref "U10") (pin "11") (pinfunction "6_11") (pintype "passive"))
      (node (ref "U2") (pin "11") (pinfunction "6_11") (pintype "passive"))
    )
    (net (code "68") (name "/X51") (class "Default")
      (node (ref "R28") (pin "2") (pinfunction "2_2") (pintype "passive"))
      (node (ref "U10") (pin "6") (pinfunction "5_6") (pintype "passive"))
      (node (ref "U2") (pin "6") (pinfunction "5_6") (pintype "passive"))
    )
    (net (code "69") (name "/X52") (class "Default")
      (node (ref "R29") (pin "2") (pinfunction "2_2") (pintype "passive"))
      (node (ref "U10") (pin "10") (pinfunction "4_10") (pintype "passive"))
      (node (ref "U2") (pin "10") (pinfunction "4_10") (pintype "passive"))
    )
    (net (code "70") (name "/X53") (class "Default")
      (node (ref "R30") (pin "2") (pinfunction "2_2") (pintype "passive"))
      (node (ref "U10") (pin "4") (pinfunction "3_4") (pintype "passive"))
      (node (ref "U2") (pin "4") (pinfunction "3_4") (pintype "passive"))
    )
    (net (code "71") (name "/X54") (class "Default")
      (node (ref "R31") (pin "2") (pinfunction "2_2") (pintype "passive"))
      (node (ref "U10") (pin "3") (pinfunction "2_3") (pintype "passive"))
      (node (ref "U2") (pin "3") (pinfunction "2_3") (pintype "passive"))
    )
    (net (code "72") (name "/X55") (class "Default")
      (node (ref "R32") (pin "2") (pinfunction "2_2") (pintype "passive"))
      (node (ref "U10") (pin "13") (pinfunction "1_13") (pintype "passive"))
      (node (ref "U2") (pin "13") (pinfunction "1_13") (pintype "passive"))
    )
    (net (code "73") (name "/X56") (class "Default")
      (node (ref "R17") (pin "2") (pinfunction "2_2") (pintype "passive"))
      (node (ref "U1") (pin "16") (pinfunction "8_16") (pintype "passive"))
      (node (ref "U9") (pin "16") (pinfunction "8_16") (pintype "passive"))
    )
    (net (code "74") (name "/X57") (class "Default")
      (node (ref "R18") (pin "2") (pinfunction "2_2") (pintype "passive"))
      (node (ref "U1") (pin "15") (pinfunction "7_15") (pintype "passive"))
      (node (ref "U9") (pin "15") (pinfunction "7_15") (pintype "passive"))
    )
    (net (code "75") (name "/X58") (class "Default")
      (node (ref "R19") (pin "2") (pinfunction "2_2") (pintype "passive"))
      (node (ref "U1") (pin "11") (pinfunction "6_11") (pintype "passive"))
      (node (ref "U9") (pin "11") (pinfunction "6_11") (pintype "passive"))
    )
    (net (code "76") (name "/X59") (class "Default")
      (node (ref "R20") (pin "2") (pinfunction "2_2") (pintype "passive"))
      (node (ref "U1") (pin "6") (pinfunction "5_6") (pintype "passive"))
      (node (ref "U9") (pin "6") (pinfunction "5_6") (pintype "passive"))
    )
    (net (code "77") (name "/X60") (class "Default")
      (node (ref "R21") (pin "2") (pinfunction "2_2") (pintype "passive"))
      (node (ref "U1") (pin "10") (pinfunction "4_10") (pintype "passive"))
      (node (ref "U9") (pin "10") (pinfunction "4_10") (pintype "passive"))
    )
    (net (code "78") (name "/X61") (class "Default")
      (node (ref "R22") (pin "2") (pinfunction "2_2") (pintype "passive"))
      (node (ref "U1") (pin "4") (pinfunction "3_4") (pintype "passive"))
      (node (ref "U9") (pin "4") (pinfunction "3_4") (pintype "passive"))
    )
    (net (code "79") (name "/X62") (class "Default")
      (node (ref "R23") (pin "2") (pinfunction "2_2") (pintype "passive"))
      (node (ref "U1") (pin "3") (pinfunction "2_3") (pintype "passive"))
      (node (ref "U9") (pin "3") (pinfunction "2_3") (pintype "passive"))
    )
    (net (code "80") (name "/X63") (class "Default")
      (node (ref "R24") (pin "2") (pinfunction "2_2") (pintype "passive"))
      (node (ref "U1") (pin "13") (pinfunction "1_13") (pintype "passive"))
      (node (ref "U9") (pin "13") (pinfunction "1_13") (pintype "passive"))
    )
    (net (code "81") (name "/Y0") (class "Default")
      (node (ref "R9") (pin "2") (pinfunction "2_2") (pintype "passive"))
      (node (ref "U10") (pin "5") (pinfunction "A_5") (pintype "passive"))
      (node (ref "U11") (pin "5") (pinfunction "A_5") (pintype "passive"))
      (node (ref "U12") (pin "5") (pinfunction "A_5") (pintype "passive"))
      (node (ref "U13") (pin "5") (pinfunction "A_5") (pintype "passive"))
      (node (ref "U14") (pin "5") (pinfunction "A_5") (pintype "passive"))
      (node (ref "U15") (pin "5") (pinfunction "A_5") (pintype "passive"))
      (node (ref "U16") (pin "5") (pinfunction "A_5") (pintype "passive"))
      (node (ref "U9") (pin "5") (pinfunction "A_5") (pintype "passive"))
    )
    (net (code "82") (name "/Y1") (class "Default")
      (node (ref "R10") (pin "2") (pinfunction "2_2") (pintype "passive"))
      (node (ref "U10") (pin "2") (pinfunction "B_2") (pintype "passive"))
      (node (ref "U11") (pin "2") (pinfunction "B_2") (pintype "passive"))
      (node (ref "U12") (pin "2") (pinfunction "B_2") (pintype "passive"))
      (node (ref "U13") (pin "2") (pinfunction "B_2") (pintype "passive"))
      (node (ref "U14") (pin "2") (pinfunction "B_2") (pintype "passive"))
      (node (ref "U15") (pin "2") (pinfunction "B_2") (pintype "passive"))
      (node (ref "U16") (pin "2") (pinfunction "B_2") (pintype "passive"))
      (node (ref "U9") (pin "2") (pinfunction "B_2") (pintype "passive"))
    )
    (net (code "83") (name "/Y2") (class "Default")
      (node (ref "R11") (pin "2") (pinfunction "2_2") (pintype "passive"))
      (node (ref "U10") (pin "7") (pinfunction "C_7") (pintype "passive"))
      (node (ref "U11") (pin "7") (pinfunction "C_7") (pintype "passive"))
      (node (ref "U12") (pin "7") (pinfunction "C_7") (pintype "passive"))
      (node (ref "U13") (pin "7") (pinfunction "C_7") (pintype "passive"))
      (node (ref "U14") (pin "7") (pinfunction "C_7") (pintype "passive"))
      (node (ref "U15") (pin "7") (pinfunction "C_7") (pintype "passive"))
      (node (ref "U16") (pin "7") (pinfunction "C_7") (pintype "passive"))
      (node (ref "U9") (pin "7") (pinfunction "C_7") (pintype "passive"))
    )
    (net (code "84") (name "/Y3") (class "Default")
      (node (ref "R12") (pin "2") (pinfunction "2_2") (pintype "passive"))
      (node (ref "U10") (pin "1") (pinfunction "D_1") (pintype "passive"))
      (node (ref "U11") (pin "1") (pinfunction "D_1") (pintype "passive"))
      (node (ref "U12") (pin "1") (pinfunction "D_1") (pintype "passive"))
      (node (ref "U13") (pin "1") (pinfunction "D_1") (pintype "passive"))
      (node (ref "U14") (pin "1") (pinfunction "D_1") (pintype "passive"))
      (node (ref "U15") (pin "1") (pinfunction "D_1") (pintype "passive"))
      (node (ref "U16") (pin "1") (pinfunction "D_1") (pintype "passive"))
      (node (ref "U9") (pin "1") (pinfunction "D_1") (pintype "passive"))
    )
    (net (code "85") (name "/Y4") (class "Default")
      (node (ref "R13") (pin "2") (pinfunction "2_2") (pintype "passive"))
      (node (ref "U10") (pin "12") (pinfunction "E_12") (pintype "passive"))
      (node (ref "U11") (pin "12") (pinfunction "E_12") (pintype "passive"))
      (node (ref "U12") (pin "12") (pinfunction "E_12") (pintype "passive"))
      (node (ref "U13") (pin "12") (pinfunction "E_12") (pintype "passive"))
      (node (ref "U14") (pin "12") (pinfunction "E_12") (pintype "passive"))
      (node (ref "U15") (pin "12") (pinfunction "E_12") (pintype "passive"))
      (node (ref "U16") (pin "12") (pinfunction "E_12") (pintype "passive"))
      (node (ref "U9") (pin "12") (pinfunction "E_12") (pintype "passive"))
    )
    (net (code "86") (name "/Y5") (class "Default")
      (node (ref "R14") (pin "2") (pinfunction "2_2") (pintype "passive"))
      (node (ref "U10") (pin "8") (pinfunction "F_8") (pintype "passive"))
      (node (ref "U11") (pin "8") (pinfunction "F_8") (pintype "passive"))
      (node (ref "U12") (pin "8") (pinfunction "F_8") (pintype "passive"))
      (node (ref "U13") (pin "8") (pinfunction "F_8") (pintype "passive"))
      (node (ref "U14") (pin "8") (pinfunction "F_8") (pintype "passive"))
      (node (ref "U15") (pin "8") (pinfunction "F_8") (pintype "passive"))
      (node (ref "U16") (pin "8") (pinfunction "F_8") (pintype "passive"))
      (node (ref "U9") (pin "8") (pinfunction "F_8") (pintype "passive"))
    )
    (net (code "87") (name "/Y6") (class "Default")
      (node (ref "R15") (pin "2") (pinfunction "2_2") (pintype "passive"))
      (node (ref "U10") (pin "14") (pinfunction "G_14") (pintype "passive"))
      (node (ref "U11") (pin "14") (pinfunction "G_14") (pintype "passive"))
      (node (ref "U12") (pin "14") (pinfunction "G_14") (pintype "passive"))
      (node (ref "U13") (pin "14") (pinfunction "G_14") (pintype "passive"))
      (node (ref "U14") (pin "14") (pinfunction "G_14") (pintype "passive"))
      (node (ref "U15") (pin "14") (pinfunction "G_14") (pintype "passive"))
      (node (ref "U16") (pin "14") (pinfunction "G_14") (pintype "passive"))
      (node (ref "U9") (pin "14") (pinfunction "G_14") (pintype "passive"))
    )
    (net (code "88") (name "/Y7") (class "Default")
      (node (ref "R16") (pin "2") (pinfunction "2_2") (pintype "passive"))
      (node (ref "U10") (pin "9") (pinfunction "H_9") (pintype "passive"))
      (node (ref "U11") (pin "9") (pinfunction "H_9") (pintype "passive"))
      (node (ref "U12") (pin "9") (pinfunction "H_9") (pintype "passive"))
      (node (ref "U13") (pin "9") (pinfunction "H_9") (pintype "passive"))
      (node (ref "U14") (pin "9") (pinfunction "H_9") (pintype "passive"))
      (node (ref "U15") (pin "9") (pinfunction "H_9") (pintype "passive"))
      (node (ref "U16") (pin "9") (pinfunction "H_9") (pintype "passive"))
      (node (ref "U9") (pin "9") (pinfunction "H_9") (pintype "passive"))
    )
    (net (code "89") (name "/Y8") (class "Default")
      (node (ref "R1") (pin "2") (pinfunction "2_2") (pintype "passive"))
      (node (ref "U1") (pin "5") (pinfunction "A_5") (pintype "passive"))
      (node (ref "U2") (pin "5") (pinfunction "A_5") (pintype "passive"))
      (node (ref "U3") (pin "5") (pinfunction "A_5") (pintype "passive"))
      (node (ref "U4") (pin "5") (pinfunction "A_5") (pintype "passive"))
      (node (ref "U5") (pin "5") (pinfunction "A_5") (pintype "passive"))
      (node (ref "U6") (pin "5") (pinfunction "A_5") (pintype "passive"))
      (node (ref "U7") (pin "5") (pinfunction "A_5") (pintype "passive"))
      (node (ref "U8") (pin "5") (pinfunction "A_5") (pintype "passive"))
    )
    (net (code "90") (name "/Y9") (class "Default")
      (node (ref "R2") (pin "2") (pinfunction "2_2") (pintype "passive"))
      (node (ref "U1") (pin "2") (pinfunction "B_2") (pintype "passive"))
      (node (ref "U2") (pin "2") (pinfunction "B_2") (pintype "passive"))
      (node (ref "U3") (pin "2") (pinfunction "B_2") (pintype "passive"))
      (node (ref "U4") (pin "2") (pinfunction "B_2") (pintype "passive"))
      (node (ref "U5") (pin "2") (pinfunction "B_2") (pintype "passive"))
      (node (ref "U6") (pin "2") (pinfunction "B_2") (pintype "passive"))
      (node (ref "U7") (pin "2") (pinfunction "B_2") (pintype "passive"))
      (node (ref "U8") (pin "2") (pinfunction "B_2") (pintype "passive"))
    )
    (net (code "91") (name "/Y10") (class "Default")
      (node (ref "R3") (pin "2") (pinfunction "2_2") (pintype "passive"))
      (node (ref "U1") (pin "7") (pinfunction "C_7") (pintype "passive"))
      (node (ref "U2") (pin "7") (pinfunction "C_7") (pintype "passive"))
      (node (ref "U3") (pin "7") (pinfunction "C_7") (pintype "passive"))
      (node (ref "U4") (pin "7") (pinfunction "C_7") (pintype "passive"))
      (node (ref "U5") (pin "7") (pinfunction "C_7") (pintype "passive"))
      (node (ref "U6") (pin "7") (pinfunction "C_7") (pintype "passive"))
      (node (ref "U7") (pin "7") (pinfunction "C_7") (pintype "passive"))
      (node (ref "U8") (pin "7") (pinfunction "C_7") (pintype "passive"))
    )
    (net (code "92") (name "/Y11") (class "Default")
      (node (ref "R4") (pin "2") (pinfunction "2_2") (pintype "passive"))
      (node (ref "U1") (pin "1") (pinfunction "D_1") (pintype "passive"))
      (node (ref "U2") (pin "1") (pinfunction "D_1") (pintype "passive"))
      (node (ref "U3") (pin "1") (pinfunction "D_1") (pintype "passive"))
      (node (ref "U4") (pin "1") (pinfunction "D_1") (pintype "passive"))
      (node (ref "U5") (pin "1") (pinfunction "D_1") (pintype "passive"))
      (node (ref "U6") (pin "1") (pinfunction "D_1") (pintype "passive"))
      (node (ref "U7") (pin "1") (pinfunction "D_1") (pintype "passive"))
      (node (ref "U8") (pin "1") (pinfunction "D_1") (pintype "passive"))
    )
    (net (code "93") (name "/Y12") (class "Default")
      (node (ref "R5") (pin "2") (pinfunction "2_2") (pintype "passive"))
      (node (ref "U1") (pin "12") (pinfunction "E_12") (pintype "passive"))
      (node (ref "U2") (pin "12") (pinfunction "E_12") (pintype "passive"))
      (node (ref "U3") (pin "12") (pinfunction "E_12") (pintype "passive"))
      (node (ref "U4") (pin "12") (pinfunction "E_12") (pintype "passive"))
      (node (ref "U5") (pin "12") (pinfunction "E_12") (pintype "passive"))
      (node (ref "U6") (pin "12") (pinfunction "E_12") (pintype "passive"))
      (node (ref "U7") (pin "12") (pinfunction "E_12") (pintype "passive"))
      (node (ref "U8") (pin "12") (pinfunction "E_12") (pintype "passive"))
    )
    (net (code "94") (name "/Y13") (class "Default")
      (node (ref "R6") (pin "2") (pinfunction "2_2") (pintype "passive"))
      (node (ref "U1") (pin "8") (pinfunction "F_8") (pintype "passive"))
      (node (ref "U2") (pin "8") (pinfunction "F_8") (pintype "passive"))
      (node (ref "U3") (pin "8") (pinfunction "F_8") (pintype "passive"))
      (node (ref "U4") (pin "8") (pinfunction "F_8") (pintype "passive"))
      (node (ref "U5") (pin "8") (pinfunction "F_8") (pintype "passive"))
      (node (ref "U6") (pin "8") (pinfunction "F_8") (pintype "passive"))
      (node (ref "U7") (pin "8") (pinfunction "F_8") (pintype "passive"))
      (node (ref "U8") (pin "8") (pinfunction "F_8") (pintype "passive"))
    )
    (net (code "95") (name "/Y14") (class "Default")
      (node (ref "R7") (pin "2") (pinfunction "2_2") (pintype "passive"))
      (node (ref "U1") (pin "14") (pinfunction "G_14") (pintype "passive"))
      (node (ref "U2") (pin "14") (pinfunction "G_14") (pintype "passive"))
      (node (ref "U3") (pin "14") (pinfunction "G_14") (pintype "passive"))
      (node (ref "U4") (pin "14") (pinfunction "G_14") (pintype "passive"))
      (node (ref "U5") (pin "14") (pinfunction "G_14") (pintype "passive"))
      (node (ref "U6") (pin "14") (pinfunction "G_14") (pintype "passive"))
      (node (ref "U7") (pin "14") (pinfunction "G_14") (pintype "passive"))
      (node (ref "U8") (pin "14") (pinfunction "G_14") (pintype "passive"))
    )
    (net (code "96") (name "/Y15") (class "Default")
      (node (ref "R8") (pin "2") (pinfunction "2_2") (pintype "passive"))
      (node (ref "U1") (pin "9") (pinfunction "H_9") (pintype "passive"))
      (node (ref "U2") (pin "9") (pinfunction "H_9") (pintype "passive"))
      (node (ref "U3") (pin "9") (pinfunction "H_9") (pintype "passive"))
      (node (ref "U4") (pin "9") (pinfunction "H_9") (pintype "passive"))
      (node (ref "U5") (pin "9") (pinfunction "H_9") (pintype "passive"))
      (node (ref "U6") (pin "9") (pinfunction "H_9") (pintype "passive"))
      (node (ref "U7") (pin "9") (pinfunction "H_9") (pintype "passive"))
      (node (ref "U8") (pin "9") (pinfunction "H_9") (pintype "passive"))
    )
    (net (code "97") (name "GND") (class "Default")
      (node (ref "C2") (pin "1") (pinfunction "1_1") (pintype "passive"))
      (node (ref "C3") (pin "1") (pinfunction "1_1") (pintype "passive"))
      (node (ref "C4") (pin "2") (pinfunction "2_2") (pintype "passive"))
      (node (ref "C5") (pin "2") (pinfunction "2_2") (pintype "passive"))
      (node (ref "P1") (pin "3") (pinfunction "3_3") (pintype "passive"))
      (node (ref "P2") (pin "1") (pinfunction "1_1") (pintype "passive"))
      (node (ref "R41") (pin "1") (pinfunction "1_1") (pintype "passive"))
      (node (ref "U17") (pin "13") (pinfunction "~{RCLR}_13") (pintype "input"))
      (node (ref "U17") (pin "8") (pinfunction "GND_8") (pintype "power_in"))
      (node (ref "U18") (pin "13") (pinfunction "~{RCLR}_13") (pintype "input"))
      (node (ref "U18") (pin "8") (pinfunction "GND_8") (pintype "power_in"))
      (node (ref "U19") (pin "13") (pinfunction "~{RCLR}_13") (pintype "input"))
      (node (ref "U19") (pin "8") (pinfunction "GND_8") (pintype "power_in"))
      (node (ref "U20") (pin "13") (pinfunction "~{RCLR}_13") (pintype "input"))
      (node (ref "U20") (pin "8") (pinfunction "GND_8") (pintype "power_in"))
      (node (ref "U21") (pin "13") (pinfunction "~{RCLR}_13") (pintype "input"))
      (node (ref "U21") (pin "8") (pinfunction "GND_8") (pintype "power_in"))
      (node (ref "U22") (pin "20") (pinfunction "GND_20") (pintype "passive"))
      (node (ref "U23") (pin "13") (pinfunction "~{RCLR}_13") (pintype "input"))
      (node (ref "U23") (pin "8") (pinfunction "GND_8") (pintype "power_in"))
      (node (ref "U24") (pin "13") (pinfunction "~{RCLR}_13") (pintype "input"))
      (node (ref "U24") (pin "8") (pinfunction "GND_8") (pintype "power_in"))
      (node (ref "U25") (pin "13") (pinfunction "~{RCLR}_13") (pintype "input"))
      (node (ref "U25") (pin "8") (pinfunction "GND_8") (pintype "power_in"))
      (node (ref "U26") (pin "13") (pinfunction "~{RCLR}_13") (pintype "input"))
      (node (ref "U26") (pin "8") (pinfunction "GND_8") (pintype "power_in"))
      (node (ref "U27") (pin "13") (pinfunction "~{RCLR}_13") (pintype "input"))
      (node (ref "U27") (pin "8") (pinfunction "GND_8") (pintype "power_in"))
    )
    (net (code "98") (name "Net-(U17-QA)") (class "Default")
      (node (ref "R1") (pin "1") (pinfunction "1_1") (pintype "passive"))
      (node (ref "U17") (pin "15") (pinfunction "QA_15") (pintype "output"))
    )
    (net (code "99") (name "Net-(U17-QB)") (class "Default")
      (node (ref "R2") (pin "1") (pinfunction "1_1") (pintype "passive"))
      (node (ref "U17") (pin "1") (pinfunction "QB_1") (pintype "output"))
    )
    (net (code "100") (name "Net-(U17-QC)") (class "Default")
      (node (ref "R3") (pin "1") (pinfunction "1_1") (pintype "passive"))
      (node (ref "U17") (pin "2") (pinfunction "QC_2") (pintype "output"))
    )
    (net (code "101") (name "Net-(U17-QD)") (class "Default")
      (node (ref "R4") (pin "1") (pinfunction "1_1") (pintype "passive"))
      (node (ref "U17") (pin "3") (pinfunction "QD_3") (pintype "output"))
    )
    (net (code "102") (name "Net-(U17-QE)") (class "Default")
      (node (ref "R5") (pin "1") (pinfunction "1_1") (pintype "passive"))
      (node (ref "U17") (pin "4") (pinfunction "QE_4") (pintype "output"))
    )
    (net (code "103") (name "Net-(U17-QF)") (class "Default")
      (node (ref "R6") (pin "1") (pinfunction "1_1") (pintype "passive"))
      (node (ref "U17") (pin "5") (pinfunction "QF_5") (pintype "output"))
    )
    (net (code "104") (name "Net-(U17-QG)") (class "Default")
      (node (ref "R7") (pin "1") (pinfunction "1_1") (pintype "passive"))
      (node (ref "U17") (pin "6") (pinfunction "QG_6") (pintype "output"))
    )
    (net (code "105") (name "Net-(U17-QH)") (class "Default")
      (node (ref "R8") (pin "1") (pinfunction "1_1") (pintype "passive"))
      (node (ref "U17") (pin "7") (pinfunction "QH_7") (pintype "output"))
    )
    (net (code "106") (name "Net-(U18-QA)") (class "Default")
      (node (ref "R9") (pin "1") (pinfunction "1_1") (pintype "passive"))
      (node (ref "U18") (pin "15") (pinfunction "QA_15") (pintype "output"))
    )
    (net (code "107") (name "Net-(U18-QB)") (class "Default")
      (node (ref "R10") (pin "1") (pinfunction "1_1") (pintype "passive"))
      (node (ref "U18") (pin "1") (pinfunction "QB_1") (pintype "output"))
    )
    (net (code "108") (name "Net-(U18-QC)") (class "Default")
      (node (ref "R11") (pin "1") (pinfunction "1_1") (pintype "passive"))
      (node (ref "U18") (pin "2") (pinfunction "QC_2") (pintype "output"))
    )
    (net (code "109") (name "Net-(U18-QD)") (class "Default")
      (node (ref "R12") (pin "1") (pinfunction "1_1") (pintype "passive"))
      (node (ref "U18") (pin "3") (pinfunction "QD_3") (pintype "output"))
    )
    (net (code "110") (name "Net-(U18-QE)") (class "Default")
      (node (ref "R13") (pin "1") (pinfunction "1_1") (pintype "passive"))
      (node (ref "U18") (pin "4") (pinfunction "QE_4") (pintype "output"))
    )
    (net (code "111") (name "Net-(U18-QF)") (class "Default")
      (node (ref "R14") (pin "1") (pinfunction "1_1") (pintype "passive"))
      (node (ref "U18") (pin "5") (pinfunction "QF_5") (pintype "output"))
    )
    (net (code "112") (name "Net-(U18-QG)") (class "Default")
      (node (ref "R15") (pin "1") (pinfunction "1_1") (pintype "passive"))
      (node (ref "U18") (pin "6") (pinfunction "QG_6") (pintype "output"))
    )
    (net (code "113") (name "Net-(U18-QH)") (class "Default")
      (node (ref "R16") (pin "1") (pinfunction "1_1") (pintype "passive"))
      (node (ref "U18") (pin "7") (pinfunction "QH_7") (pintype "output"))
    )
    (net (code "114") (name "Net-(U19-QA)") (class "Default")
      (node (ref "R17") (pin "1") (pinfunction "1_1") (pintype "passive"))
      (node (ref "U19") (pin "15") (pinfunction "QA_15") (pintype "output"))
    )
    (net (code "115") (name "Net-(U19-QB)") (class "Default")
      (node (ref "R18") (pin "1") (pinfunction "1_1") (pintype "passive"))
      (node (ref "U19") (pin "1") (pinfunction "QB_1") (pintype "output"))
    )
    (net (code "116") (name "Net-(U19-QC)") (class "Default")
      (node (ref "R19") (pin "1") (pinfunction "1_1") (pintype "passive"))
      (node (ref "U19") (pin "2") (pinfunction "QC_2") (pintype "output"))
    )
    (net (code "117") (name "Net-(U19-QD)") (class "Default")
      (node (ref "R20") (pin "1") (pinfunction "1_1") (pintype "passive"))
      (node (ref "U19") (pin "3") (pinfunction "QD_3") (pintype "output"))
    )
    (net (code "118") (name "Net-(U19-QE)") (class "Default")
      (node (ref "R21") (pin "1") (pinfunction "1_1") (pintype "passive"))
      (node (ref "U19") (pin "4") (pinfunction "QE_4") (pintype "output"))
    )
    (net (code "119") (name "Net-(U19-QF)") (class "Default")
      (node (ref "R22") (pin "1") (pinfunction "1_1") (pintype "passive"))
      (node (ref "U19") (pin "5") (pinfunction "QF_5") (pintype "output"))
    )
    (net (code "120") (name "Net-(U19-QG)") (class "Default")
      (node (ref "R23") (pin "1") (pinfunction "1_1") (pintype "passive"))
      (node (ref "U19") (pin "6") (pinfunction "QG_6") (pintype "output"))
    )
    (net (code "121") (name "Net-(U19-QH)") (class "Default")
      (node (ref "R24") (pin "1") (pinfunction "1_1") (pintype "passive"))
      (node (ref "U19") (pin "7") (pinfunction "QH_7") (pintype "output"))
    )
    (net (code "122") (name "Net-(U20-QA)") (class "Default")
      (node (ref "R25") (pin "1") (pinfunction "1_1") (pintype "passive"))
      (node (ref "U20") (pin "15") (pinfunction "QA_15") (pintype "output"))
    )
    (net (code "123") (name "Net-(U20-QB)") (class "Default")
      (node (ref "R26") (pin "1") (pinfunction "1_1") (pintype "passive"))
      (node (ref "U20") (pin "1") (pinfunction "QB_1") (pintype "output"))
    )
    (net (code "124") (name "Net-(U20-QC)") (class "Default")
      (node (ref "R27") (pin "1") (pinfunction "1_1") (pintype "passive"))
      (node (ref "U20") (pin "2") (pinfunction "QC_2") (pintype "output"))
    )
    (net (code "125") (name "Net-(U20-QD)") (class "Default")
      (node (ref "R28") (pin "1") (pinfunction "1_1") (pintype "passive"))
      (node (ref "U20") (pin "3") (pinfunction "QD_3") (pintype "output"))
    )
    (net (code "126") (name "Net-(U20-QE)") (class "Default")
      (node (ref "R29") (pin "1") (pinfunction "1_1") (pintype "passive"))
      (node (ref "U20") (pin "4") (pinfunction "QE_4") (pintype "output"))
    )
    (net (code "127") (name "Net-(U20-QF)") (class "Default")
      (node (ref "R30") (pin "1") (pinfunction "1_1") (pintype "passive"))
      (node (ref "U20") (pin "5") (pinfunction "QF_5") (pintype "output"))
    )
    (net (code "128") (name "Net-(U20-QG)") (class "Default")
      (node (ref "R31") (pin "1") (pinfunction "1_1") (pintype "passive"))
      (node (ref "U20") (pin "6") (pinfunction "QG_6") (pintype "output"))
    )
    (net (code "129") (name "Net-(U20-QH)") (class "Default")
      (node (ref "R32") (pin "1") (pinfunction "1_1") (pintype "passive"))
      (node (ref "U20") (pin "7") (pinfunction "QH_7") (pintype "output"))
    )
    (net (code "130") (name "Net-(U21-QA)") (class "Default")
      (node (ref "R33") (pin "1") (pinfunction "1_1") (pintype "passive"))
      (node (ref "U21") (pin "15") (pinfunction "QA_15") (pintype "output"))
    )
    (net (code "131") (name "Net-(U21-QB)") (class "Default")
      (node (ref "R34") (pin "1") (pinfunction "1_1") (pintype "passive"))
      (node (ref "U21") (pin "1") (pinfunction "QB_1") (pintype "output"))
    )
    (net (code "132") (name "Net-(U21-QC)") (class "Default")
      (node (ref "R35") (pin "1") (pinfunction "1_1") (pintype "passive"))
      (node (ref "U21") (pin "2") (pinfunction "QC_2") (pintype "output"))
    )
    (net (code "133") (name "Net-(U21-QD)") (class "Default")
      (node (ref "R36") (pin "1") (pinfunction "1_1") (pintype "passive"))
      (node (ref "U21") (pin "3") (pinfunction "QD_3") (pintype "output"))
    )
    (net (code "134") (name "Net-(U21-QE)") (class "Default")
      (node (ref "R37") (pin "1") (pinfunction "1_1") (pintype "passive"))
      (node (ref "U21") (pin "4") (pinfunction "QE_4") (pintype "output"))
    )
    (net (code "135") (name "Net-(U21-QF)") (class "Default")
      (node (ref "R38") (pin "1") (pinfunction "1_1") (pintype "passive"))
      (node (ref "U21") (pin "5") (pinfunction "QF_5") (pintype "output"))
    )
    (net (code "136") (name "Net-(U21-QG)") (class "Default")
      (node (ref "R39") (pin "1") (pinfunction "1_1") (pintype "passive"))
      (node (ref "U21") (pin "6") (pinfunction "QG_6") (pintype "output"))
    )
    (net (code "137") (name "Net-(U21-QH)") (class "Default")
      (node (ref "R40") (pin "1") (pinfunction "1_1") (pintype "passive"))
      (node (ref "U21") (pin "7") (pinfunction "QH_7") (pintype "output"))
    )
    (net (code "138") (name "Net-(U22-EA{slash}Vpp)") (class "Default")
      (node (ref "R42") (pin "2") (pinfunction "2_2") (pintype "passive"))
      (node (ref "U22") (pin "31") (pinfunction "EA/Vpp_31") (pintype "passive"))
    )
    (net (code "139") (name "Net-(U22-RST{slash}VPD)") (class "Default")
      (node (ref "C1") (pin "2") (pinfunction "2_2") (pintype "passive"))
      (node (ref "R41") (pin "2") (pinfunction "2_2") (pintype "passive"))
      (node (ref "S1") (pin "1") (pinfunction "1_1") (pintype "passive"))
      (node (ref "U22") (pin "9") (pinfunction "RST/VPD_9") (pintype "passive"))
    )
    (net (code "140") (name "Net-(U22-XTAL1)") (class "Default")
      (node (ref "C3") (pin "2") (pinfunction "2_2") (pintype "passive"))
      (node (ref "U22") (pin "19") (pinfunction "XTAL1_19") (pintype "passive"))
      (node (ref "Y1") (pin "1") (pinfunction "OSC1_1") (pintype "passive"))
    )
    (net (code "141") (name "Net-(U22-XTAL2)") (class "Default")
      (node (ref "C2") (pin "2") (pinfunction "2_2") (pintype "passive"))
      (node (ref "U22") (pin "18") (pinfunction "XTAL2_18") (pintype "passive"))
      (node (ref "Y1") (pin "2") (pinfunction "OSC2_2") (pintype "passive"))
    )
    (net (code "142") (name "Net-(U23-QA)") (class "Default")
      (node (ref "R43") (pin "1") (pinfunction "1_1") (pintype "passive"))
      (node (ref "U23") (pin "15") (pinfunction "QA_15") (pintype "output"))
    )
    (net (code "143") (name "Net-(U23-QB)") (class "Default")
      (node (ref "R44") (pin "1") (pinfunction "1_1") (pintype "passive"))
      (node (ref "U23") (pin "1") (pinfunction "QB_1") (pintype "output"))
    )
    (net (code "144") (name "Net-(U23-QC)") (class "Default")
      (node (ref "R45") (pin "1") (pinfunction "1_1") (pintype "passive"))
      (node (ref "U23") (pin "2") (pinfunction "QC_2") (pintype "output"))
    )
    (net (code "145") (name "Net-(U23-QD)") (class "Default")
      (node (ref "R46") (pin "1") (pinfunction "1_1") (pintype "passive"))
      (node (ref "U23") (pin "3") (pinfunction "QD_3") (pintype "output"))
    )
    (net (code "146") (name "Net-(U23-QE)") (class "Default")
      (node (ref "R47") (pin "1") (pinfunction "1_1") (pintype "passive"))
      (node (ref "U23") (pin "4") (pinfunction "QE_4") (pintype "output"))
    )
    (net (code "147") (name "Net-(U23-QF)") (class "Default")
      (node (ref "R48") (pin "1") (pinfunction "1_1") (pintype "passive"))
      (node (ref "U23") (pin "5") (pinfunction "QF_5") (pintype "output"))
    )
    (net (code "148") (name "Net-(U23-QG)") (class "Default")
      (node (ref "R49") (pin "1") (pinfunction "1_1") (pintype "passive"))
      (node (ref "U23") (pin "6") (pinfunction "QG_6") (pintype "output"))
    )
    (net (code "149") (name "Net-(U23-QH)") (class "Default")
      (node (ref "R50") (pin "1") (pinfunction "1_1") (pintype "passive"))
      (node (ref "U23") (pin "7") (pinfunction "QH_7") (pintype "output"))
    )
    (net (code "150") (name "Net-(U24-QA)") (class "Default")
      (node (ref "R51") (pin "1") (pinfunction "1_1") (pintype "passive"))
      (node (ref "U24") (pin "15") (pinfunction "QA_15") (pintype "output"))
    )
    (net (code "151") (name "Net-(U24-QB)") (class "Default")
      (node (ref "R52") (pin "1") (pinfunction "1_1") (pintype "passive"))
      (node (ref "U24") (pin "1") (pinfunction "QB_1") (pintype "output"))
    )
    (net (code "152") (name "Net-(U24-QC)") (class "Default")
      (node (ref "R53") (pin "1") (pinfunction "1_1") (pintype "passive"))
      (node (ref "U24") (pin "2") (pinfunction "QC_2") (pintype "output"))
    )
    (net (code "153") (name "Net-(U24-QD)") (class "Default")
      (node (ref "R54") (pin "1") (pinfunction "1_1") (pintype "passive"))
      (node (ref "U24") (pin "3") (pinfunction "QD_3") (pintype "output"))
    )
    (net (code "154") (name "Net-(U24-QE)") (class "Default")
      (node (ref "R55") (pin "1") (pinfunction "1_1") (pintype "passive"))
      (node (ref "U24") (pin "4") (pinfunction "QE_4") (pintype "output"))
    )
    (net (code "155") (name "Net-(U24-QF)") (class "Default")
      (node (ref "R56") (pin "1") (pinfunction "1_1") (pintype "passive"))
      (node (ref "U24") (pin "5") (pinfunction "QF_5") (pintype "output"))
    )
    (net (code "156") (name "Net-(U24-QG)") (class "Default")
      (node (ref "R57") (pin "1") (pinfunction "1_1") (pintype "passive"))
      (node (ref "U24") (pin "6") (pinfunction "QG_6") (pintype "output"))
    )
    (net (code "157") (name "Net-(U24-QH)") (class "Default")
      (node (ref "R58") (pin "1") (pinfunction "1_1") (pintype "passive"))
      (node (ref "U24") (pin "7") (pinfunction "QH_7") (pintype "output"))
    )
    (net (code "158") (name "Net-(U25-QA)") (class "Default")
      (node (ref "R59") (pin "1") (pinfunction "1_1") (pintype "passive"))
      (node (ref "U25") (pin "15") (pinfunction "QA_15") (pintype "output"))
    )
    (net (code "159") (name "Net-(U25-QB)") (class "Default")
      (node (ref "R60") (pin "1") (pinfunction "1_1") (pintype "passive"))
      (node (ref "U25") (pin "1") (pinfunction "QB_1") (pintype "output"))
    )
    (net (code "160") (name "Net-(U25-QC)") (class "Default")
      (node (ref "R61") (pin "1") (pinfunction "1_1") (pintype "passive"))
      (node (ref "U25") (pin "2") (pinfunction "QC_2") (pintype "output"))
    )
    (net (code "161") (name "Net-(U25-QD)") (class "Default")
      (node (ref "R62") (pin "1") (pinfunction "1_1") (pintype "passive"))
      (node (ref "U25") (pin "3") (pinfunction "QD_3") (pintype "output"))
    )
    (net (code "162") (name "Net-(U25-QE)") (class "Default")
      (node (ref "R63") (pin "1") (pinfunction "1_1") (pintype "passive"))
      (node (ref "U25") (pin "4") (pinfunction "QE_4") (pintype "output"))
    )
    (net (code "163") (name "Net-(U25-QF)") (class "Default")
      (node (ref "R64") (pin "1") (pinfunction "1_1") (pintype "passive"))
      (node (ref "U25") (pin "5") (pinfunction "QF_5") (pintype "output"))
    )
    (net (code "164") (name "Net-(U25-QG)") (class "Default")
      (node (ref "R65") (pin "1") (pinfunction "1_1") (pintype "passive"))
      (node (ref "U25") (pin "6") (pinfunction "QG_6") (pintype "output"))
    )
    (net (code "165") (name "Net-(U25-QH)") (class "Default")
      (node (ref "R66") (pin "1") (pinfunction "1_1") (pintype "passive"))
      (node (ref "U25") (pin "7") (pinfunction "QH_7") (pintype "output"))
    )
    (net (code "166") (name "Net-(U26-QA)") (class "Default")
      (node (ref "R67") (pin "1") (pinfunction "1_1") (pintype "passive"))
      (node (ref "U26") (pin "15") (pinfunction "QA_15") (pintype "output"))
    )
    (net (code "167") (name "Net-(U26-QB)") (class "Default")
      (node (ref "R68") (pin "1") (pinfunction "1_1") (pintype "passive"))
      (node (ref "U26") (pin "1") (pinfunction "QB_1") (pintype "output"))
    )
    (net (code "168") (name "Net-(U26-QC)") (class "Default")
      (node (ref "R69") (pin "1") (pinfunction "1_1") (pintype "passive"))
      (node (ref "U26") (pin "2") (pinfunction "QC_2") (pintype "output"))
    )
    (net (code "169") (name "Net-(U26-QD)") (class "Default")
      (node (ref "R70") (pin "1") (pinfunction "1_1") (pintype "passive"))
      (node (ref "U26") (pin "3") (pinfunction "QD_3") (pintype "output"))
    )
    (net (code "170") (name "Net-(U26-QE)") (class "Default")
      (node (ref "R71") (pin "1") (pinfunction "1_1") (pintype "passive"))
      (node (ref "U26") (pin "4") (pinfunction "QE_4") (pintype "output"))
    )
    (net (code "171") (name "Net-(U26-QF)") (class "Default")
      (node (ref "R72") (pin "1") (pinfunction "1_1") (pintype "passive"))
      (node (ref "U26") (pin "5") (pinfunction "QF_5") (pintype "output"))
    )
    (net (code "172") (name "Net-(U26-QG)") (class "Default")
      (node (ref "R73") (pin "1") (pinfunction "1_1") (pintype "passive"))
      (node (ref "U26") (pin "6") (pinfunction "QG_6") (pintype "output"))
    )
    (net (code "173") (name "Net-(U26-QH)") (class "Default")
      (node (ref "R74") (pin "1") (pinfunction "1_1") (pintype "passive"))
      (node (ref "U26") (pin "7") (pinfunction "QH_7") (pintype "output"))
    )
    (net (code "174") (name "Net-(U27-QA)") (class "Default")
      (node (ref "R75") (pin "1") (pinfunction "1_1") (pintype "passive"))
      (node (ref "U27") (pin "15") (pinfunction "QA_15") (pintype "output"))
    )
    (net (code "175") (name "Net-(U27-QB)") (class "Default")
      (node (ref "R76") (pin "1") (pinfunction "1_1") (pintype "passive"))
      (node (ref "U27") (pin "1") (pinfunction "QB_1") (pintype "output"))
    )
    (net (code "176") (name "Net-(U27-QC)") (class "Default")
      (node (ref "R77") (pin "1") (pinfunction "1_1") (pintype "passive"))
      (node (ref "U27") (pin "2") (pinfunction "QC_2") (pintype "output"))
    )
    (net (code "177") (name "Net-(U27-QD)") (class "Default")
      (node (ref "R78") (pin "1") (pinfunction "1_1") (pintype "passive"))
      (node (ref "U27") (pin "3") (pinfunction "QD_3") (pintype "output"))
    )
    (net (code "178") (name "Net-(U27-QE)") (class "Default")
      (node (ref "R79") (pin "1") (pinfunction "1_1") (pintype "passive"))
      (node (ref "U27") (pin "4") (pinfunction "QE_4") (pintype "output"))
    )
    (net (code "179") (name "Net-(U27-QF)") (class "Default")
      (node (ref "R80") (pin "1") (pinfunction "1_1") (pintype "passive"))
      (node (ref "U27") (pin "5") (pinfunction "QF_5") (pintype "output"))
    )
    (net (code "180") (name "Net-(U27-QG)") (class "Default")
      (node (ref "R81") (pin "1") (pinfunction "1_1") (pintype "passive"))
      (node (ref "U27") (pin "6") (pinfunction "QG_6") (pintype "output"))
    )
    (net (code "181") (name "Net-(U27-QH)") (class "Default")
      (node (ref "R82") (pin "1") (pinfunction "1_1") (pintype "passive"))
      (node (ref "U27") (pin "7") (pinfunction "QH_7") (pintype "output"))
    )
    (net (code "182") (name "VCC") (class "Default")
      (node (ref "C1") (pin "1") (pinfunction "1_1") (pintype "passive"))
      (node (ref "P1") (pin "2") (pinfunction "2_2") (pintype "passive"))
      (node (ref "R42") (pin "1") (pinfunction "1_1") (pintype "passive"))
      (node (ref "S1") (pin "2") (pinfunction "2_2") (pintype "passive"))
      (node (ref "S2") (pin "2") (pinfunction "NO1_2") (pintype "passive"))
      (node (ref "S2") (pin "4") (pinfunction "NO2_4") (pintype "passive"))
      (node (ref "U17") (pin "10") (pinfunction "~{SRCLR}_10") (pintype "input"))
      (node (ref "U17") (pin "16") (pinfunction "VCC_16") (pintype "power_in"))
      (node (ref "U18") (pin "10") (pinfunction "~{SRCLR}_10") (pintype "input"))
      (node (ref "U18") (pin "16") (pinfunction "VCC_16") (pintype "power_in"))
      (node (ref "U19") (pin "10") (pinfunction "~{SRCLR}_10") (pintype "input"))
      (node (ref "U19") (pin "16") (pinfunction "VCC_16") (pintype "power_in"))
      (node (ref "U20") (pin "10") (pinfunction "~{SRCLR}_10") (pintype "input"))
      (node (ref "U20") (pin "16") (pinfunction "VCC_16") (pintype "power_in"))
      (node (ref "U21") (pin "10") (pinfunction "~{SRCLR}_10") (pintype "input"))
      (node (ref "U21") (pin "16") (pinfunction "VCC_16") (pintype "power_in"))
      (node (ref "U23") (pin "10") (pinfunction "~{SRCLR}_10") (pintype "input"))
      (node (ref "U23") (pin "16") (pinfunction "VCC_16") (pintype "power_in"))
      (node (ref "U24") (pin "10") (pinfunction "~{SRCLR}_10") (pintype "input"))
      (node (ref "U24") (pin "16") (pinfunction "VCC_16") (pintype "power_in"))
      (node (ref "U25") (pin "10") (pinfunction "~{SRCLR}_10") (pintype "input"))
      (node (ref "U25") (pin "16") (pinfunction "VCC_16") (pintype "power_in"))
      (node (ref "U26") (pin "10") (pinfunction "~{SRCLR}_10") (pintype "input"))
      (node (ref "U26") (pin "16") (pinfunction "VCC_16") (pintype "power_in"))
      (node (ref "U27") (pin "10") (pinfunction "~{SRCLR}_10") (pintype "input"))
      (node (ref "U27") (pin "16") (pinfunction "VCC_16") (pintype "power_in"))
    )
    (net (code "183") (name "unconnected-(P2-Pad2)") (class "Default")
      (node (ref "P2") (pin "2") (pinfunction "2_2") (pintype "passive"))
    )
    (net (code "184") (name "unconnected-(P2-Pad3)") (class "Default")
      (node (ref "P2") (pin "3") (pinfunction "3_3") (pintype "passive"))
    )
    (net (code "185") (name "unconnected-(P2-Pad4)") (class "Default")
      (node (ref "P2") (pin "4") (pinfunction "4_4") (pintype "passive"))
    )
    (net (code "186") (name "unconnected-(R53-Pad2)") (class "Default")
      (node (ref "R53") (pin "2") (pinfunction "2_2") (pintype "passive"))
    )
    (net (code "187") (name "unconnected-(U17-QH'-Pad9)") (class "Default")
      (node (ref "U17") (pin "9") (pinfunction "QH'_9") (pintype "output"))
    )
    (net (code "188") (name "unconnected-(U22-ALE{slash}PROG-Pad30)") (class "Default")
      (node (ref "U22") (pin "30") (pinfunction "ALE/PROG_30") (pintype "passive"))
    )
    (net (code "189") (name "unconnected-(U22-P0.3-Pad36)") (class "Default")
      (node (ref "U22") (pin "36") (pinfunction "P0.3_36") (pintype "passive"))
    )
    (net (code "190") (name "unconnected-(U22-P0.4-Pad35)") (class "Default")
      (node (ref "U22") (pin "35") (pinfunction "P0.4_35") (pintype "passive"))
    )
    (net (code "191") (name "unconnected-(U22-P0.5-Pad34)") (class "Default")
      (node (ref "U22") (pin "34") (pinfunction "P0.5_34") (pintype "passive"))
    )
    (net (code "192") (name "unconnected-(U22-P0.6-Pad33)") (class "Default")
      (node (ref "U22") (pin "33") (pinfunction "P0.6_33") (pintype "passive"))
    )
    (net (code "193") (name "unconnected-(U22-P0.7-Pad32)") (class "Default")
      (node (ref "U22") (pin "32") (pinfunction "P0.7_32") (pintype "passive"))
    )
    (net (code "194") (name "unconnected-(U22-P1.0-Pad1)") (class "Default")
      (node (ref "U22") (pin "1") (pinfunction "P1.0_1") (pintype "passive"))
    )
    (net (code "195") (name "unconnected-(U22-P1.1-Pad2)") (class "Default")
      (node (ref "U22") (pin "2") (pinfunction "P1.1_2") (pintype "passive"))
    )
    (net (code "196") (name "unconnected-(U22-P1.2-Pad3)") (class "Default")
      (node (ref "U22") (pin "3") (pinfunction "P1.2_3") (pintype "passive"))
    )
    (net (code "197") (name "unconnected-(U22-P1.3-Pad4)") (class "Default")
      (node (ref "U22") (pin "4") (pinfunction "P1.3_4") (pintype "passive"))
    )
    (net (code "198") (name "unconnected-(U22-P1.4-Pad5)") (class "Default")
      (node (ref "U22") (pin "5") (pinfunction "P1.4_5") (pintype "passive"))
    )
    (net (code "199") (name "unconnected-(U22-P1.5-Pad6)") (class "Default")
      (node (ref "U22") (pin "6") (pinfunction "P1.5_6") (pintype "passive"))
    )
    (net (code "200") (name "unconnected-(U22-P1.6-Pad7)") (class "Default")
      (node (ref "U22") (pin "7") (pinfunction "P1.6_7") (pintype "passive"))
    )
    (net (code "201") (name "unconnected-(U22-P1.7-Pad8)") (class "Default")
      (node (ref "U22") (pin "8") (pinfunction "P1.7_8") (pintype "passive"))
    )
    (net (code "202") (name "unconnected-(U22-P2.0-Pad21)") (class "Default")
      (node (ref "U22") (pin "21") (pinfunction "P2.0_21") (pintype "passive"))
    )
    (net (code "203") (name "unconnected-(U22-P2.1-Pad22)") (class "Default")
      (node (ref "U22") (pin "22") (pinfunction "P2.1_22") (pintype "passive"))
    )
    (net (code "204") (name "unconnected-(U22-P2.2-Pad23)") (class "Default")
      (node (ref "U22") (pin "23") (pinfunction "P2.2_23") (pintype "passive"))
    )
    (net (code "205") (name "unconnected-(U22-P2.3-Pad24)") (class "Default")
      (node (ref "U22") (pin "24") (pinfunction "P2.3_24") (pintype "passive"))
    )
    (net (code "206") (name "unconnected-(U22-P2.4-Pad25)") (class "Default")
      (node (ref "U22") (pin "25") (pinfunction "P2.4_25") (pintype "passive"))
    )
    (net (code "207") (name "unconnected-(U22-P2.5-Pad26)") (class "Default")
      (node (ref "U22") (pin "26") (pinfunction "P2.5_26") (pintype "passive"))
    )
    (net (code "208") (name "unconnected-(U22-P2.6-Pad27)") (class "Default")
      (node (ref "U22") (pin "27") (pinfunction "P2.6_27") (pintype "passive"))
    )
    (net (code "209") (name "unconnected-(U22-P2.7-Pad28)") (class "Default")
      (node (ref "U22") (pin "28") (pinfunction "P2.7_28") (pintype "passive"))
    )
    (net (code "210") (name "unconnected-(U22-P3.2{slash}INT0-Pad12)") (class "Default")
      (node (ref "U22") (pin "12") (pinfunction "P3.2/INT0_12") (pintype "passive"))
    )
    (net (code "211") (name "unconnected-(U22-P3.3{slash}INT1-Pad13)") (class "Default")
      (node (ref "U22") (pin "13") (pinfunction "P3.3/INT1_13") (pintype "passive"))
    )
    (net (code "212") (name "unconnected-(U22-P3.4{slash}T0-Pad14)") (class "Default")
      (node (ref "U22") (pin "14") (pinfunction "P3.4/T0_14") (pintype "passive"))
    )
    (net (code "213") (name "unconnected-(U22-P3.5{slash}T1-Pad15)") (class "Default")
      (node (ref "U22") (pin "15") (pinfunction "P3.5/T1_15") (pintype "passive"))
    )
    (net (code "214") (name "unconnected-(U22-P3.6{slash}WR-Pad16)") (class "Default")
      (node (ref "U22") (pin "16") (pinfunction "P3.6/WR_16") (pintype "passive"))
    )
    (net (code "215") (name "unconnected-(U22-P3.7{slash}RD-Pad17)") (class "Default")
      (node (ref "U22") (pin "17") (pinfunction "P3.7/RD_17") (pintype "passive"))
    )
    (net (code "216") (name "unconnected-(U22-PSEN-Pad29)") (class "Default")
      (node (ref "U22") (pin "29") (pinfunction "PSEN_29") (pintype "passive"))
    )
    (net (code "217") (name "unconnected-(U22-VCC-Pad40)") (class "Default")
      (node (ref "U22") (pin "40") (pinfunction "VCC_40") (pintype "passive"))
    )
  )
)
